# 261503933xxxx_HW-V1.net
KiCad netlist of a schematic drawn in EAGLE
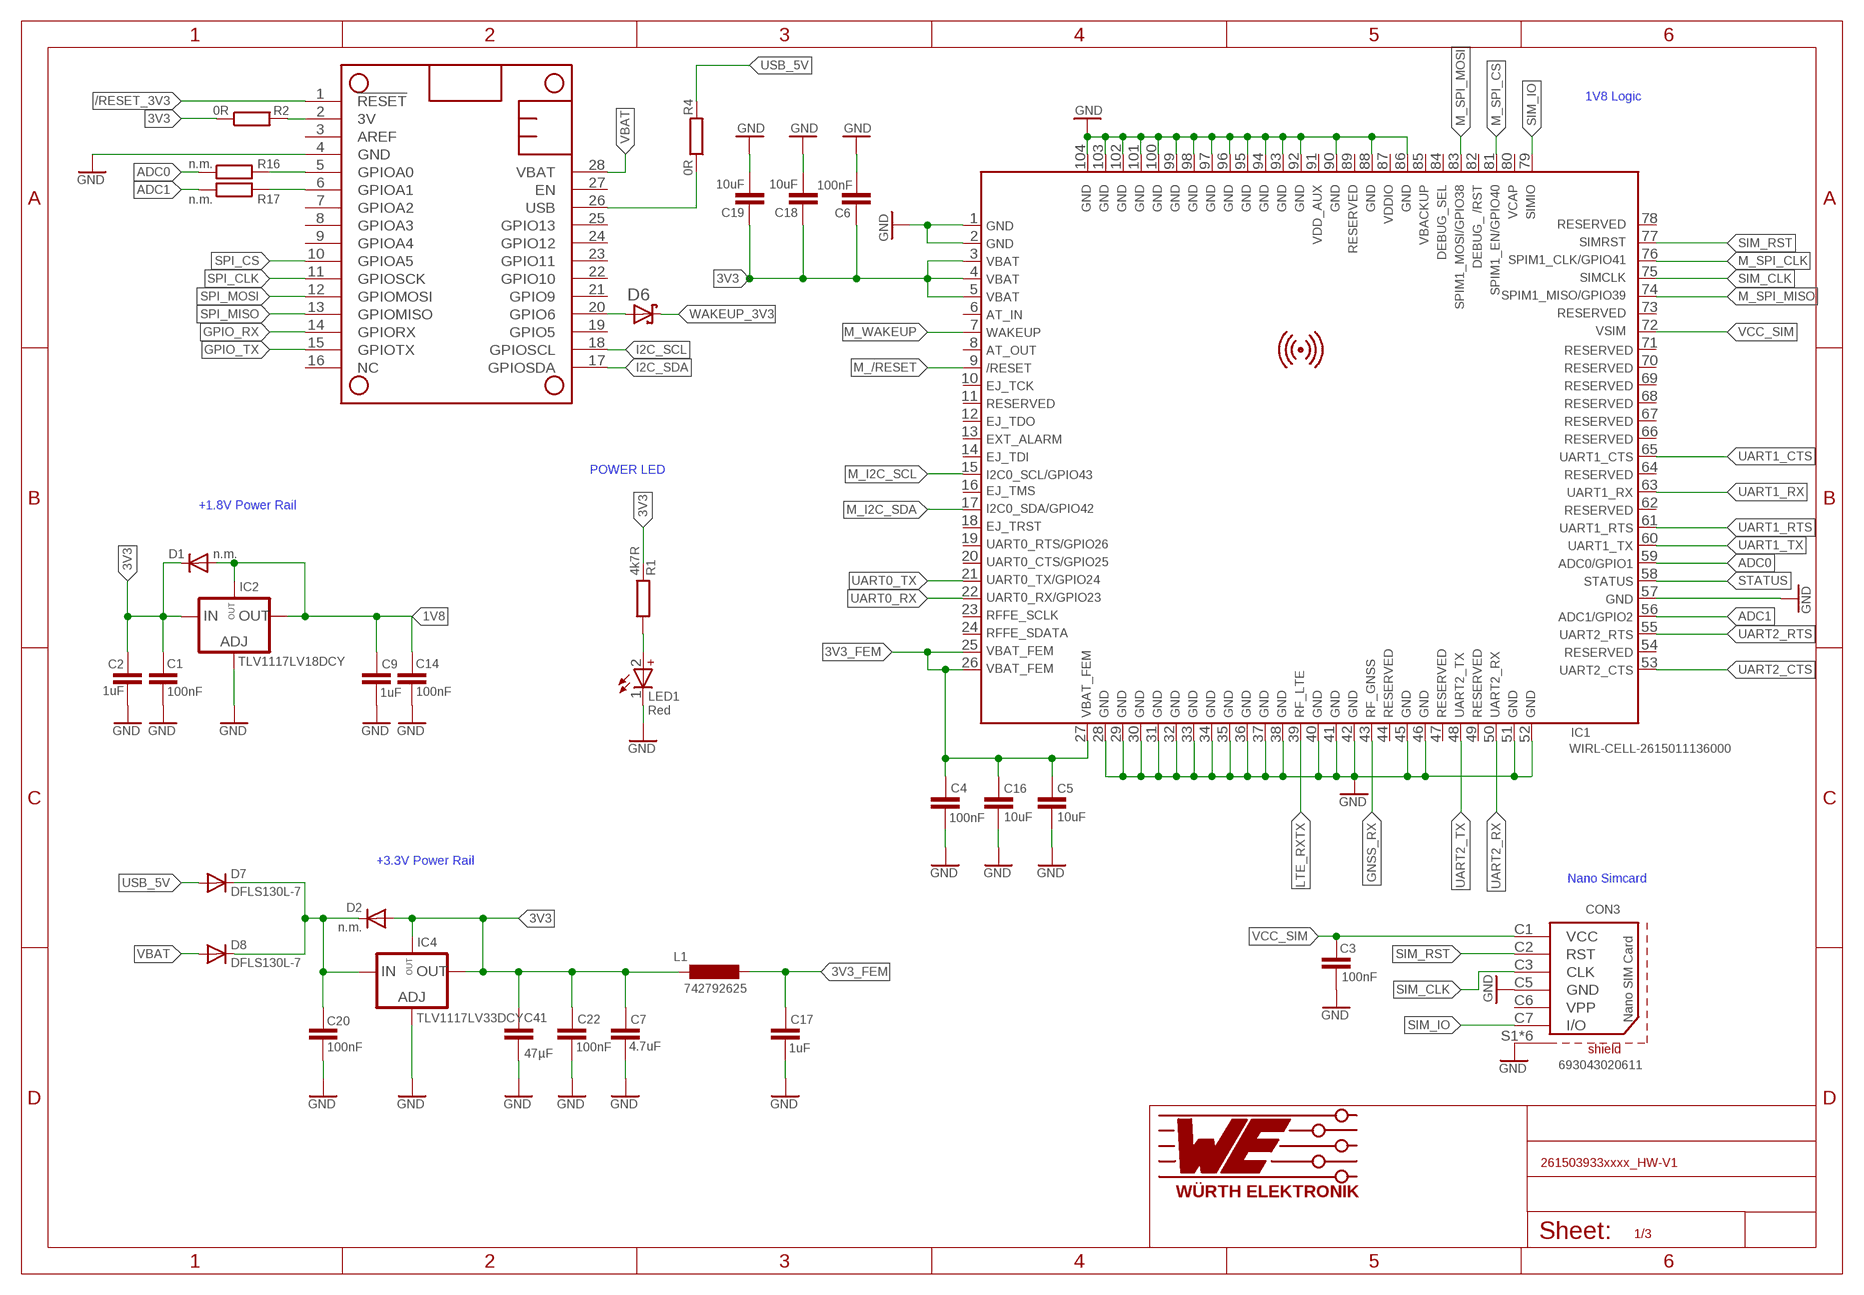
[diagram p0: schematic, sheet 1]
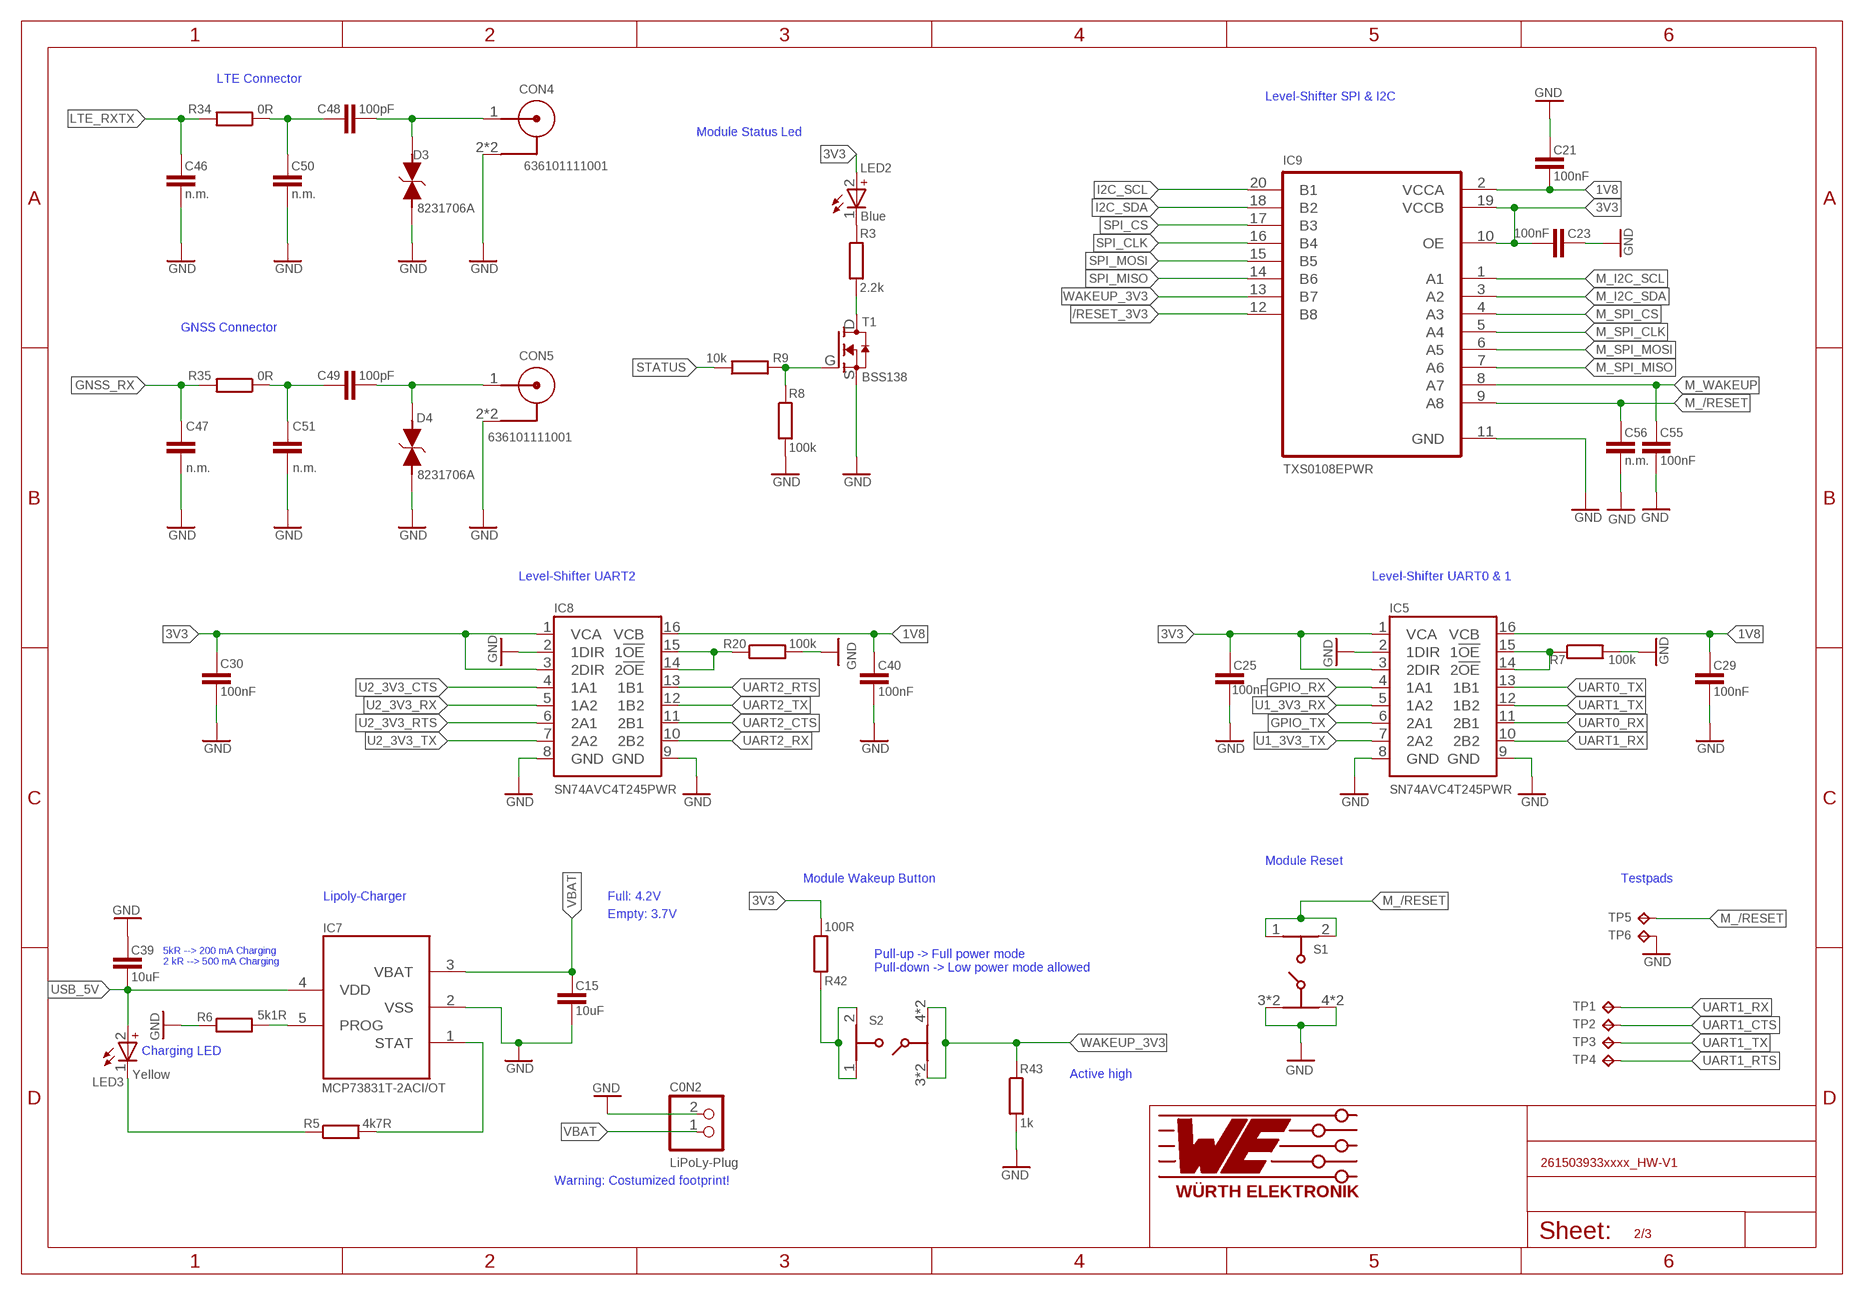
[diagram p1: schematic, sheet 2]
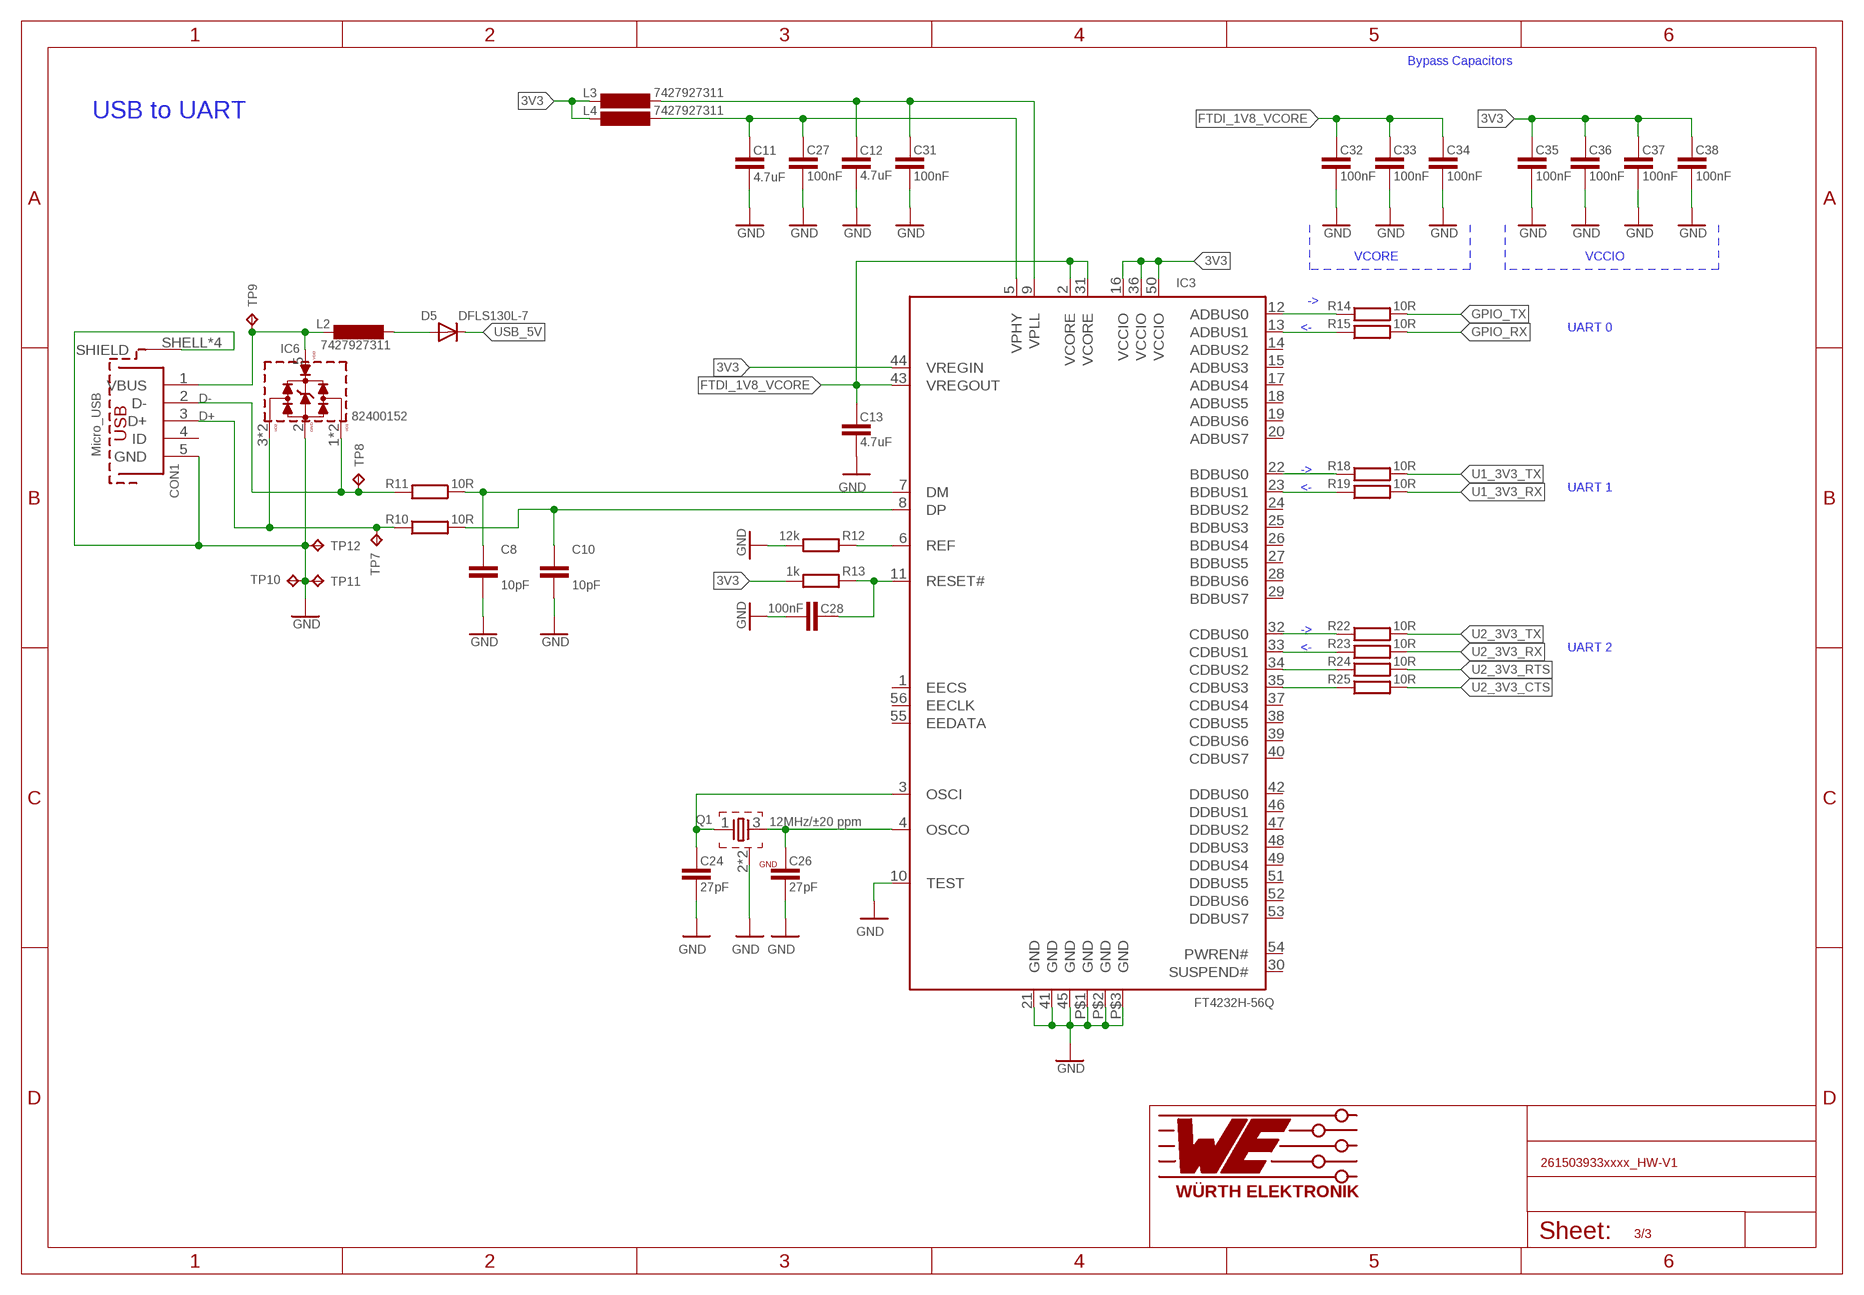
[diagram p2: schematic, sheet 3]

(export (version "E")
  (design (tool "Eeschema 10.0.6"))
  (components
    (comp (ref "C0N2")
      (value "LiPoLy-Plug")
      (footprint "eagle-import:JST-PH-2-SMT-RA-ADRASTEA-ANGEPASST")
      (fields (field (name "MANUFACTURER") "Adafruit"))
      (libsource (lib "eagle-import") (part "JST_2PIN"))
    )
    (comp (ref "C15")
      (value "10uF")
      (footprint "eagle-import:C0402_IPC")
      (fields (field (name "MANUFACTURER") "Würth Elektronik"))
      (libsource (lib "eagle-import") (part "C0402_IPC10UF"))
    )
    (comp (ref "C21")
      (value "100nF")
      (footprint "eagle-import:C0402_IPC")
      (fields
        (field (name "MANUFACTURER") "Würth Elektronik")
        (field (name "MAT") "X7R")
        (field (name "NR") "885012205037")
        (field (name "SPG") "16V")
        (field (name "TOL") "10%")
      )
      (libsource (lib "eagle-import") (part "rcl-amber_C0402_IPC"))
    )
    (comp (ref "C23")
      (value "100nF")
      (footprint "eagle-import:C0402_IPC")
      (fields
        (field (name "MANUFACTURER") "Würth Elektronik")
        (field (name "MAT") "X7R")
        (field (name "NR") "885012205037")
        (field (name "SPG") "16V")
        (field (name "TOL") "10%")
      )
      (libsource (lib "eagle-import") (part "rcl-amber_C0402_IPC"))
    )
    (comp (ref "C25")
      (value "100nF")
      (footprint "eagle-import:C0402_IPC")
      (fields
        (field (name "MANUFACTURER") "Würth Elektronik")
        (field (name "MAT") "X7R")
        (field (name "NR") "885012205037")
        (field (name "SPG") "16V")
        (field (name "TOL") "10%")
      )
      (libsource (lib "eagle-import") (part "rcl-amber_C0402_IPC"))
    )
    (comp (ref "C29")
      (value "100nF")
      (footprint "eagle-import:C0402_IPC")
      (fields
        (field (name "MANUFACTURER") "Würth Elektronik")
        (field (name "MAT") "X7R")
        (field (name "NR") "885012205037")
        (field (name "SPG") "16V")
        (field (name "TOL") "10%")
      )
      (libsource (lib "eagle-import") (part "rcl-amber_C0402_IPC"))
    )
    (comp (ref "C30")
      (value "100nF")
      (footprint "eagle-import:C0402_IPC")
      (fields
        (field (name "MANUFACTURER") "Würth Elektronik")
        (field (name "MAT") "X7R")
        (field (name "NR") "885012205037")
        (field (name "SPG") "16V")
        (field (name "TOL") "10%")
      )
      (libsource (lib "eagle-import") (part "rcl-amber_C0402_IPC"))
    )
    (comp (ref "C39")
      (value "10uF")
      (footprint "eagle-import:C0603_IPC")
      (fields (field (name "MANUFACTURER") "Wurth Elektronik") (field (name "NR") "885012106031"))
      (libsource (lib "eagle-import") (part "C0603_IPC1UF"))
    )
    (comp (ref "C40")
      (value "100nF")
      (footprint "eagle-import:C0402_IPC")
      (fields
        (field (name "MANUFACTURER") "Würth Elektronik")
        (field (name "MAT") "X7R")
        (field (name "NR") "885012205037")
        (field (name "SPG") "16V")
        (field (name "TOL") "10%")
      )
      (libsource (lib "eagle-import") (part "rcl-amber_C0402_IPC"))
    )
    (comp (ref "C46")
      (value "n.m.")
      (footprint "eagle-import:C0402_IPC")
      (fields (field (name "MANUFACTURER") "n.m.") (field (name "NR") "n.m."))
      (libsource (lib "eagle-import") (part "rcl-amber_C0402_IPC"))
    )
    (comp (ref "C47")
      (value "n.m.")
      (footprint "eagle-import:C0402_IPC")
      (fields (field (name "MANUFACTURER") "n.m.") (field (name "NR") "n.m."))
      (libsource (lib "eagle-import") (part "rcl-amber_C0402_IPC"))
    )
    (comp (ref "C48")
      (value "100pF")
      (footprint "eagle-import:C0402_IPC")
      (fields
        (field (name "MANUFACTURER") "Yageo")
        (field (name "MANUFACTURER_1") "Würth Elektronik")
        (field (name "MAT") "NP0")
        (field (name "NR") "885012005061")
      )
      (libsource (lib "eagle-import") (part "rcl-amber_C0402_IPC100PF"))
    )
    (comp (ref "C49")
      (value "100pF")
      (footprint "eagle-import:C0402_IPC")
      (fields
        (field (name "MANUFACTURER") "Würth Elektronik")
        (field (name "MAT") "NP0")
        (field (name "NR") "885012005061")
        (field (name "SPG") "50V")
        (field (name "TOL") "5%")
      )
      (libsource (lib "eagle-import") (part "rcl-amber_C0402_IPC"))
    )
    (comp (ref "C50")
      (value "n.m.")
      (footprint "eagle-import:C0402_IPC")
      (fields (field (name "MANUFACTURER") "n.m.") (field (name "NR") "n.m."))
      (libsource (lib "eagle-import") (part "rcl-amber_C0402_IPC"))
    )
    (comp (ref "C51")
      (value "n.m.")
      (footprint "eagle-import:C0402_IPC")
      (fields (field (name "MANUFACTURER") "n.m.") (field (name "NR") "n.m."))
      (libsource (lib "eagle-import") (part "rcl-amber_C0402_IPC"))
    )
    (comp (ref "C55")
      (value "100nF")
      (footprint "eagle-import:C0402_IPC")
      (fields
        (field (name "MANUFACTURER") "Würth Elektronik")
        (field (name "MAT") "X7R")
        (field (name "NR") "885012205037")
        (field (name "SPG") "16V")
        (field (name "TOL") "10%")
      )
      (libsource (lib "eagle-import") (part "rcl-amber_C0402_IPC"))
    )
    (comp (ref "C56")
      (value "n.m.")
      (footprint "eagle-import:C0402_IPC")
      (fields (field (name "MANUFACTURER") "n.m.") (field (name "NR") "n.m."))
      (libsource (lib "eagle-import") (part "rcl-amber_C0402_IPC"))
    )
    (comp (ref "CON4")
      (value "636101111001")
      (footprint "eagle-import:636101111001")
      (libsource (lib "eagle-import") (part "636101111001"))
    )
    (comp (ref "CON5")
      (value "636101111001")
      (footprint "eagle-import:636101111001")
      (libsource (lib "eagle-import") (part "636101111001"))
    )
    (comp (ref "D3")
      (value "8231706A")
      (footprint "eagle-import:WE-VE_FEMTOF_0402")
      (fields (field (name "MANUFACTURER") "Würth Elektronik"))
      (libsource (lib "eagle-import") (part "WE-VE_FEMTOF_0402_8231714A"))
    )
    (comp (ref "D4")
      (value "8231706A")
      (footprint "eagle-import:WE-VE_FEMTOF_0402")
      (fields (field (name "MANUFACTURER") "Würth Elektronik"))
      (libsource (lib "eagle-import") (part "WE-VE_FEMTOF_0402_8231714A"))
    )
    (comp (ref "IC5")
      (value "SN74AVC4T245PWR")
      (footprint "eagle-import:PW16(TSSOP16)")
      (fields (field (name "MANUFACTURER") "Texas Instruments"))
      (libsource (lib "eagle-import") (part "SN74AVC4T245PWR"))
    )
    (comp (ref "IC7")
      (value "MCP73831T-2ACI/OT")
      (footprint "eagle-import:SOT23-5")
      (fields (field (name "MANUFACTURER") "microchip"))
      (libsource (lib "eagle-import") (part "MCP73831T-2ACI/OT"))
    )
    (comp (ref "IC8")
      (value "SN74AVC4T245PWR")
      (footprint "eagle-import:PW16(TSSOP16)")
      (fields (field (name "MANUFACTURER") "Texas Instruments"))
      (libsource (lib "eagle-import") (part "SN74AVC4T245PWR"))
    )
    (comp (ref "IC9")
      (value "TXS0108EPWR")
      (footprint "eagle-import:SOP65P640X120-20N")
      (fields (field (name "MF") "Texas Instruments"))
      (libsource (lib "eagle-import") (part "TXS0108EPWR"))
    )
    (comp (ref "LED2")
      (value "Blue")
      (footprint "eagle-import:WL-SMSW_1204_A")
      (fields (field (name "MANUFACTURER") "würth elektronik"))
      (libsource (lib "eagle-import") (part "WL-SMSW_1204_155124BS73200"))
    )
    (comp (ref "LED3")
      (value "Yellow")
      (footprint "eagle-import:WL-SMSW_1204_A")
      (fields (field (name "MANUFACTURER") "würth elektronik"))
      (libsource (lib "eagle-import") (part "WL-SMSW_1204_155124RS73200"))
    )
    (comp (ref "R3")
      (value "2.2k")
      (footprint "eagle-import:R0402_IPC")
      (fields (field (name "MANUFACTURER") "Yageo") (field (name "P") "1/16W"))
      (libsource (lib "eagle-import") (part "R0402_IPC2K2"))
    )
    (comp (ref "R5")
      (value "4k7R")
      (footprint "eagle-import:R0402_IPC")
      (fields (field (name "MANUFACTURER") "Yageo"))
      (libsource (lib "eagle-import") (part "R0402_IPC4K7"))
    )
    (comp (ref "R6")
      (value "5k1R")
      (footprint "eagle-import:R0402_IPC")
      (fields (field (name "NR") " RC0402FR-075K1L"))
      (libsource (lib "eagle-import") (part "R0402_IPC56R"))
    )
    (comp (ref "R7")
      (value "100k")
      (footprint "eagle-import:R0402_IPC")
      (libsource (lib "eagle-import") (part "R0402_IPC100KR"))
    )
    (comp (ref "R8")
      (value "100k")
      (footprint "eagle-import:R0402_IPC")
      (fields (field (name "MANUFACTURER") "Yageo") (field (name "P") "1/16W"))
      (libsource (lib "eagle-import") (part "rcl-amber_R0402_IPC100KR"))
    )
    (comp (ref "R9")
      (value "10k")
      (footprint "eagle-import:R0402_IPC")
      (fields (field (name "MANUFACTURER") "Yageo") (field (name "P") "1/16W"))
      (libsource (lib "eagle-import") (part "rcl-amber_R0402_IPC10KR"))
    )
    (comp (ref "R20")
      (value "100k")
      (footprint "eagle-import:R0402_IPC")
      (libsource (lib "eagle-import") (part "R0402_IPC100KR"))
    )
    (comp (ref "R34")
      (value "0R")
      (footprint "eagle-import:R0402_IPC")
      (fields (field (name "MANUFACTURER") "Yageo") (field (name "P") "1/16W"))
      (libsource (lib "eagle-import") (part "rcl-amber_R0402_IPC0R"))
    )
    (comp (ref "R35")
      (value "0R")
      (footprint "eagle-import:R0402_IPC")
      (fields (field (name "MANUFACTURER") "Yageo") (field (name "P") "1/16W"))
      (libsource (lib "eagle-import") (part "rcl-amber_R0402_IPC0R"))
    )
    (comp (ref "R42")
      (value "100R")
      (footprint "eagle-import:R0402_IPC")
      (fields (field (name "MANUFACTURER") "Yageo"))
      (libsource (lib "eagle-import") (part "R0402_IPC100R"))
    )
    (comp (ref "R43")
      (value "1k")
      (footprint "eagle-import:R0402_IPC")
      (fields (field (name "MANUFACTURER") "Yageo") (field (name "P") "1/16W"))
      (libsource (lib "eagle-import") (part "R0402_IPC1K"))
    )
    (comp (ref "S1")
      (value "434331013822")
      (footprint "eagle-import:434331013822")
      (libsource (lib "eagle-import") (part "434331013822"))
    )
    (comp (ref "S2")
      (value "434331013822")
      (footprint "eagle-import:434331013822")
      (libsource (lib "eagle-import") (part "434331013822"))
    )
    (comp (ref "T1")
      (value "BSS138")
      (footprint "eagle-import:BSS138")
      (fields (field (name "MANUFACTURER") "ON seminconductor"))
      (libsource (lib "eagle-import") (part "BSS138"))
    )
    (comp (ref "TP1")
      (value "TP15R")
      (footprint "eagle-import:TP15R")
      (libsource (lib "eagle-import") (part "TP15R"))
    )
    (comp (ref "TP2")
      (value "TP15R")
      (footprint "eagle-import:TP15R")
      (libsource (lib "eagle-import") (part "TP15R"))
    )
    (comp (ref "TP3")
      (value "TP15R")
      (footprint "eagle-import:TP15R")
      (libsource (lib "eagle-import") (part "TP15R"))
    )
    (comp (ref "TP4")
      (value "TP15R")
      (footprint "eagle-import:TP15R")
      (libsource (lib "eagle-import") (part "TP15R"))
    )
    (comp (ref "TP5")
      (value "TP15R")
      (footprint "eagle-import:TP15R")
      (libsource (lib "eagle-import") (part "TP15R"))
    )
    (comp (ref "TP6")
      (value "TP15R")
      (footprint "eagle-import:TP15R")
      (libsource (lib "eagle-import") (part "TP15R"))
    )
    (comp (ref "C8")
      (value "10pF")
      (footprint "eagle-import:C0402_IPC")
      (fields (field (name "MANUFACTURER") "Würth Elektronik") (field (name "MAT") "NP0"))
      (libsource (lib "eagle-import") (part "C0402_IPC10PF"))
    )
    (comp (ref "C10")
      (value "10pF")
      (footprint "eagle-import:C0402_IPC")
      (fields (field (name "MANUFACTURER") "Würth Elektronik") (field (name "MAT") "NP0"))
      (libsource (lib "eagle-import") (part "C0402_IPC10PF"))
    )
    (comp (ref "C11")
      (value "4.7uF")
      (footprint "eagle-import:C0402_IPC")
      (fields (field (name "MANUFACTURER") "Würth Elektronik"))
      (libsource (lib "eagle-import") (part "C0402_IPC4.7UF"))
    )
    (comp (ref "C12")
      (value "4.7uF")
      (footprint "eagle-import:C0402_IPC")
      (fields (field (name "MANUFACTURER") "Würth Elektronik"))
      (libsource (lib "eagle-import") (part "C0402_IPC4.7UF"))
    )
    (comp (ref "C13")
      (value "4.7uF")
      (footprint "eagle-import:C0402_IPC")
      (fields (field (name "MANUFACTURER") "Würth Elektronik"))
      (libsource (lib "eagle-import") (part "C0402_IPC4.7UF"))
    )
    (comp (ref "C24")
      (value "27pF")
      (footprint "eagle-import:C0402_IPC")
      (fields
        (field (name "MANUFACTURER") "Yageo")
        (field (name "MANUFACTURER_1") "Samsung")
        (field (name "NR") "CL05C270JB5NNNC")
      )
      (libsource (lib "eagle-import") (part "C0402_IPC27P"))
    )
    (comp (ref "C26")
      (value "27pF")
      (footprint "eagle-import:C0402_IPC")
      (fields
        (field (name "MANUFACTURER") "Yageo")
        (field (name "MANUFACTURER_1") "Samsung")
        (field (name "NR") "CL05C270JB5NNNC")
      )
      (libsource (lib "eagle-import") (part "C0402_IPC27P"))
    )
    (comp (ref "C27")
      (value "100nF")
      (footprint "eagle-import:C0402_IPC")
      (fields
        (field (name "MANUFACTURER") "Würth Elektronik")
        (field (name "MAT") "X7R")
        (field (name "NR") "885012205037")
        (field (name "SPG") "16V")
        (field (name "TOL") "10%")
      )
      (libsource (lib "eagle-import") (part "rcl-amber_C0402_IPC"))
    )
    (comp (ref "C28")
      (value "100nF")
      (footprint "eagle-import:C0402_IPC")
      (fields
        (field (name "MANUFACTURER") "Würth Elektronik")
        (field (name "MAT") "X7R")
        (field (name "NR") "885012205037")
        (field (name "SPG") "16V")
        (field (name "TOL") "10%")
      )
      (libsource (lib "eagle-import") (part "rcl-amber_C0402_IPC"))
    )
    (comp (ref "C31")
      (value "100nF")
      (footprint "eagle-import:C0402_IPC")
      (fields
        (field (name "MANUFACTURER") "Würth Elektronik")
        (field (name "MAT") "X7R")
        (field (name "NR") "885012205037")
        (field (name "SPG") "16V")
        (field (name "TOL") "10%")
      )
      (libsource (lib "eagle-import") (part "rcl-amber_C0402_IPC"))
    )
    (comp (ref "C32")
      (value "100nF")
      (footprint "eagle-import:C0402_IPC")
      (fields
        (field (name "MANUFACTURER") "Würth Elektronik")
        (field (name "MAT") "X7R")
        (field (name "NR") "885012205037")
        (field (name "SPG") "16V")
        (field (name "TOL") "10%")
      )
      (libsource (lib "eagle-import") (part "rcl-amber_C0402_IPC"))
    )
    (comp (ref "C33")
      (value "100nF")
      (footprint "eagle-import:C0402_IPC")
      (fields
        (field (name "MANUFACTURER") "Würth Elektronik")
        (field (name "MAT") "X7R")
        (field (name "NR") "885012205037")
        (field (name "SPG") "16V")
        (field (name "TOL") "10%")
      )
      (libsource (lib "eagle-import") (part "rcl-amber_C0402_IPC"))
    )
    (comp (ref "C34")
      (value "100nF")
      (footprint "eagle-import:C0402_IPC")
      (fields
        (field (name "MANUFACTURER") "Würth Elektronik")
        (field (name "MAT") "X7R")
        (field (name "NR") "885012205037")
        (field (name "SPG") "16V")
        (field (name "TOL") "10%")
      )
      (libsource (lib "eagle-import") (part "rcl-amber_C0402_IPC"))
    )
    (comp (ref "C35")
      (value "100nF")
      (footprint "eagle-import:C0402_IPC")
      (fields
        (field (name "MANUFACTURER") "Würth Elektronik")
        (field (name "MAT") "X7R")
        (field (name "NR") "885012205037")
        (field (name "SPG") "16V")
        (field (name "TOL") "10%")
      )
      (libsource (lib "eagle-import") (part "rcl-amber_C0402_IPC"))
    )
    (comp (ref "C36")
      (value "100nF")
      (footprint "eagle-import:C0402_IPC")
      (fields
        (field (name "MANUFACTURER") "Würth Elektronik")
        (field (name "MAT") "X7R")
        (field (name "NR") "885012205037")
        (field (name "SPG") "16V")
        (field (name "TOL") "10%")
      )
      (libsource (lib "eagle-import") (part "rcl-amber_C0402_IPC"))
    )
    (comp (ref "C37")
      (value "100nF")
      (footprint "eagle-import:C0402_IPC")
      (fields
        (field (name "MANUFACTURER") "Würth Elektronik")
        (field (name "MAT") "X7R")
        (field (name "NR") "885012205037")
        (field (name "SPG") "16V")
        (field (name "TOL") "10%")
      )
      (libsource (lib "eagle-import") (part "rcl-amber_C0402_IPC"))
    )
    (comp (ref "C38")
      (value "100nF")
      (footprint "eagle-import:C0402_IPC")
      (fields
        (field (name "MANUFACTURER") "Würth Elektronik")
        (field (name "MAT") "X7R")
        (field (name "NR") "885012205037")
        (field (name "SPG") "16V")
        (field (name "TOL") "10%")
      )
      (libsource (lib "eagle-import") (part "rcl-amber_C0402_IPC"))
    )
    (comp (ref "CON1")
      (value "Micro_USB")
      (footprint "eagle-import:629105150521")
      (fields
        (field (name "COMMENT") "Use selective soldering")
        (field (name "MANUFACTURER") "Würth Elektronik")
      )
      (libsource (lib "eagle-import") (part "629105150521"))
    )
    (comp (ref "D5")
      (value "DFLS130L-7")
      (footprint "eagle-import:SOD123_POWERDI")
      (fields (field (name "MANUFACTURER") "diodes inc"))
      (libsource (lib "eagle-import") (part "DFLS130L-7"))
    )
    (comp (ref "IC3")
      (value "FT4232H-56Q")
      (footprint "eagle-import:VQFN-56")
      (fields (field (name "MANUFACTURER") "FTDI"))
      (libsource (lib "eagle-import") (part "FT4232H-56Q"))
    )
    (comp (ref "IC6")
      (value "82400152")
      (footprint "eagle-import:WE-TVS_SOT563")
      (fields (field (name "MANUFACTURER") "Würth Elektronik"))
      (libsource (lib "eagle-import") (part "WE-TVS_82400152"))
    )
    (comp (ref "L2")
      (value "7427927311")
      (footprint "eagle-import:L0402_WE-MK")
      (fields
        (field (name "MANUFACTURER") "Tayo Yuden")
        (field (name "MANUFACTURER_1") "Würth Elektronik")
        (field (name "NR") "7427927311")
      )
      (libsource (lib "eagle-import") (part "LL0402_WE-MK"))
    )
    (comp (ref "L3")
      (value "7427927311")
      (footprint "eagle-import:L0402_WE-MK")
      (fields
        (field (name "MANUFACTURER") "Tayo Yuden")
        (field (name "MANUFACTURER_1") "Würth Elektronik")
        (field (name "NR") "7427927311")
      )
      (libsource (lib "eagle-import") (part "LL0402_WE-MK"))
    )
    (comp (ref "L4")
      (value "7427927311")
      (footprint "eagle-import:L0402_WE-MK")
      (fields
        (field (name "MANUFACTURER") "Tayo Yuden")
        (field (name "MANUFACTURER_1") "Würth Elektronik")
        (field (name "NR") "7427927311")
      )
      (libsource (lib "eagle-import") (part "LL0402_WE-MK"))
    )
    (comp (ref "Q1")
      (value "12MHz/±20 ppm")
      (footprint "eagle-import:WE-XTAL_CFPX-180")
      (fields (field (name "MANUFACTURER") "Würth Elektronik"))
      (libsource (lib "eagle-import") (part "WE-XTAL_CFPX-180_830070868"))
    )
    (comp (ref "R10")
      (value "10R")
      (footprint "eagle-import:R0402_IPC")
      (fields (field (name "MANUFACTURER") "Yageo"))
      (libsource (lib "eagle-import") (part "rcl-amber_R0402_IPC10R"))
    )
    (comp (ref "R11")
      (value "10R")
      (footprint "eagle-import:R0402_IPC")
      (fields (field (name "MANUFACTURER") "Yageo"))
      (libsource (lib "eagle-import") (part "rcl-amber_R0402_IPC10R"))
    )
    (comp (ref "R12")
      (value "12k")
      (footprint "eagle-import:R0402_IPC")
      (fields (field (name "MANUFACTURER") "Yageo") (field (name "P") "1/16W"))
      (libsource (lib "eagle-import") (part "R0402_IPC12K"))
    )
    (comp (ref "R13")
      (value "1k")
      (footprint "eagle-import:R0402_IPC")
      (fields (field (name "MANUFACTURER") "Yageo"))
      (libsource (lib "eagle-import") (part "R0402_IPC1K"))
    )
    (comp (ref "R14")
      (value "10R")
      (footprint "eagle-import:R0402_IPC")
      (fields (field (name "MANUFACTURER") "Yageo"))
      (libsource (lib "eagle-import") (part "rcl-amber_R0402_IPC10R"))
    )
    (comp (ref "R15")
      (value "10R")
      (footprint "eagle-import:R0402_IPC")
      (fields (field (name "MANUFACTURER") "Yageo"))
      (libsource (lib "eagle-import") (part "rcl-amber_R0402_IPC10R"))
    )
    (comp (ref "R18")
      (value "10R")
      (footprint "eagle-import:R0402_IPC")
      (fields (field (name "MANUFACTURER") "Yageo"))
      (libsource (lib "eagle-import") (part "rcl-amber_R0402_IPC10R"))
    )
    (comp (ref "R19")
      (value "10R")
      (footprint "eagle-import:R0402_IPC")
      (fields (field (name "MANUFACTURER") "Yageo"))
      (libsource (lib "eagle-import") (part "rcl-amber_R0402_IPC10R"))
    )
    (comp (ref "R22")
      (value "10R")
      (footprint "eagle-import:R0402_IPC")
      (fields (field (name "MANUFACTURER") "Yageo"))
      (libsource (lib "eagle-import") (part "rcl-amber_R0402_IPC10R"))
    )
    (comp (ref "R23")
      (value "10R")
      (footprint "eagle-import:R0402_IPC")
      (fields (field (name "MANUFACTURER") "Yageo"))
      (libsource (lib "eagle-import") (part "rcl-amber_R0402_IPC10R"))
    )
    (comp (ref "R24")
      (value "10R")
      (footprint "eagle-import:R0402_IPC")
      (fields (field (name "MANUFACTURER") "Yageo"))
      (libsource (lib "eagle-import") (part "rcl-amber_R0402_IPC10R"))
    )
    (comp (ref "R25")
      (value "10R")
      (footprint "eagle-import:R0402_IPC")
      (fields (field (name "MANUFACTURER") "Yageo"))
      (libsource (lib "eagle-import") (part "rcl-amber_R0402_IPC10R"))
    )
    (comp (ref "TP7")
      (value "TP15R")
      (footprint "eagle-import:TP15R")
      (libsource (lib "eagle-import") (part "TP15R"))
    )
    (comp (ref "TP8")
      (value "TP15R")
      (footprint "eagle-import:TP15R")
      (libsource (lib "eagle-import") (part "TP15R"))
    )
    (comp (ref "TP9")
      (value "TP15R")
      (footprint "eagle-import:TP15R")
      (libsource (lib "eagle-import") (part "TP15R"))
    )
    (comp (ref "TP10")
      (value "TP15R")
      (footprint "eagle-import:TP15R")
      (libsource (lib "eagle-import") (part "TP15R"))
    )
    (comp (ref "TP11")
      (value "TP15R")
      (footprint "eagle-import:TP15R")
      (libsource (lib "eagle-import") (part "TP15R"))
    )
    (comp (ref "TP12")
      (value "TP15R")
      (footprint "eagle-import:TP15R")
      (libsource (lib "eagle-import") (part "TP15R"))
    )
    (comp (ref "C1")
      (value "100nF")
      (footprint "eagle-import:C0402_IPC")
      (fields
        (field (name "MANUFACTURER") "Würth Elektronik")
        (field (name "MAT") "X7R")
        (field (name "NR") "885012205037")
        (field (name "SPG") "16V")
        (field (name "TOL") "10%")
      )
      (libsource (lib "eagle-import") (part "rcl-amber_C0402_IPC"))
    )
    (comp (ref "C2")
      (value "1uF")
      (footprint "eagle-import:C0402_IPC")
      (fields (field (name "MANUFACTURER") "Würth Elektronik"))
      (libsource (lib "eagle-import") (part "C0402_IPC1UF"))
    )
    (comp (ref "C3")
      (value "100nF")
      (footprint "eagle-import:C0402_IPC")
      (fields (field (name "MANUFACTURER") "Würth Elektronik"))
      (libsource (lib "eagle-import") (part "C0402_IPC100NF"))
    )
    (comp (ref "C4")
      (value "100nF")
      (footprint "eagle-import:C0402_IPC")
      (fields
        (field (name "MANUFACTURER") "Würth Elektronik")
        (field (name "MAT") "X7R")
        (field (name "NR") "885012205037")
        (field (name "SPG") "16V")
        (field (name "TOL") "10%")
      )
      (libsource (lib "eagle-import") (part "rcl-amber_C0402_IPC"))
    )
    (comp (ref "C5")
      (value "10uF")
      (footprint "eagle-import:C0402_IPC")
      (fields
        (field (name "MANUFACTURER") "Würth Elektronik")
        (field (name "NR") "885012105020")
        (field (name "SPG") "6,3V")
      )
      (libsource (lib "eagle-import") (part "C0402_IPC"))
    )
    (comp (ref "C6")
      (value "100nF")
      (footprint "eagle-import:C0402_IPC")
      (fields
        (field (name "MANUFACTURER") "Würth Elektronik")
        (field (name "MAT") "X7R")
        (field (name "NR") "885012205037")
        (field (name "SPG") "16V")
        (field (name "TOL") "10%")
      )
      (libsource (lib "eagle-import") (part "rcl-amber_C0402_IPC"))
    )
    (comp (ref "C7")
      (value "4.7uF")
      (footprint "eagle-import:C0402_IPC")
      (fields (field (name "MANUFACTURER") "Würth Elektronik"))
      (libsource (lib "eagle-import") (part "C0402_IPC4.7UF"))
    )
    (comp (ref "C9")
      (value "1uF")
      (footprint "eagle-import:C0402_IPC")
      (fields (field (name "MANUFACTURER") "Würth Elektronik"))
      (libsource (lib "eagle-import") (part "C0402_IPC1UF"))
    )
    (comp (ref "C14")
      (value "100nF")
      (footprint "eagle-import:C0402_IPC")
      (fields
        (field (name "MANUFACTURER") "Würth Elektronik")
        (field (name "MAT") "X7R")
        (field (name "NR") "885012205037")
        (field (name "SPG") "16V")
        (field (name "TOL") "10%")
      )
      (libsource (lib "eagle-import") (part "rcl-amber_C0402_IPC"))
    )
    (comp (ref "C16")
      (value "10uF")
      (footprint "eagle-import:C0402_IPC")
      (fields
        (field (name "MANUFACTURER") "Würth Elektronik")
        (field (name "MAT") "X5R")
        (field (name "NR") "885012105020")
        (field (name "SPG") "6,3V")
        (field (name "TOL") "20%")
      )
      (libsource (lib "eagle-import") (part "C0402_IPC"))
    )
    (comp (ref "C17")
      (value "1uF")
      (footprint "eagle-import:C0402_IPC")
      (fields (field (name "MANUFACTURER") "Würth Elektronik"))
      (libsource (lib "eagle-import") (part "C0402_IPC1UF"))
    )
    (comp (ref "C18")
      (value "10uF")
      (footprint "eagle-import:C0402_IPC")
      (fields
        (field (name "MANUFACTURER") "Würth Elektronik")
        (field (name "NR") "885012105020")
        (field (name "SPG") "6,3V")
      )
      (libsource (lib "eagle-import") (part "C0402_IPC"))
    )
    (comp (ref "C19")
      (value "10uF")
      (footprint "eagle-import:C0402_IPC")
      (fields
        (field (name "MANUFACTURER") "Würth Elektronik")
        (field (name "NR") "885012105020")
        (field (name "SPG") "6,3V")
      )
      (libsource (lib "eagle-import") (part "C0402_IPC"))
    )
    (comp (ref "C20")
      (value "100nF")
      (footprint "eagle-import:C0402_IPC")
      (fields
        (field (name "MANUFACTURER") "Würth Elektronik")
        (field (name "MAT") "X7R")
        (field (name "NR") "885012205037")
        (field (name "SPG") "16V")
        (field (name "TOL") "10%")
      )
      (libsource (lib "eagle-import") (part "rcl-amber_C0402_IPC"))
    )
    (comp (ref "C22")
      (value "100nF")
      (footprint "eagle-import:C0402_IPC")
      (fields
        (field (name "MANUFACTURER") "Würth Elektronik")
        (field (name "MAT") "X7R")
        (field (name "NR") "885012205037")
        (field (name "SPG") "16V")
        (field (name "TOL") "10%")
      )
      (libsource (lib "eagle-import") (part "rcl-amber_C0402_IPC"))
    )
    (comp (ref "C41")
      (value "47µF")
      (footprint "eagle-import:C0805")
      (fields (field (name "MANUFACTURER") "Wurth Elektronik"))
      (libsource (lib "eagle-import") (part "C080547UF"))
    )
    (comp (ref "CON3")
      (value "693043020611")
      (footprint "eagle-import:693043020611")
      (libsource (lib "eagle-import") (part "693043020611"))
    )
    (comp (ref "D1")
      (value "n.m.")
      (footprint "eagle-import:SOT23@1")
      (libsource (lib "eagle-import") (part "BAS16"))
    )
    (comp (ref "D2")
      (value "n.m.")
      (footprint "eagle-import:SOT23@1")
      (libsource (lib "eagle-import") (part "BAS16"))
    )
    (comp (ref "D6")
      (value "BAT540402_X1-DFN1006-2")
      (footprint "eagle-import:X1-DFN1006-2")
      (fields (field (name "MANUFACTURER") "Diodes Inc."))
      (libsource (lib "eagle-import") (part "BAT540402_X1-DFN1006-2"))
    )
    (comp (ref "D7")
      (value "DFLS130L-7")
      (footprint "eagle-import:SOD123_POWERDI")
      (fields (field (name "MANUFACTURER") "diodes inc"))
      (libsource (lib "eagle-import") (part "DFLS130L-7"))
    )
    (comp (ref "D8")
      (value "DFLS130L-7")
      (footprint "eagle-import:SOD123_POWERDI")
      (fields (field (name "MANUFACTURER") "diodes inc"))
      (libsource (lib "eagle-import") (part "DFLS130L-7"))
    )
    (comp (ref "IC1")
      (value "WIRL-CELL-2615011136000")
      (footprint "eagle-import:WIRL-CELL-2615011136000")
      (fields (field (name "MANUFACTURER") "Wuerth Elektronik"))
      (libsource (lib "eagle-import") (part "WIRL-CELL-2615011136000"))
    )
    (comp (ref "IC2")
      (value "TLV1117LV18DCY")
      (footprint "eagle-import:SOT223-4")
      (fields (field (name "MANUFACTURER") "Texas Instruments"))
      (libsource (lib "eagle-import") (part "TLV1117-XXIDCYR"))
    )
    (comp (ref "IC4")
      (value "TLV1117LV33DCY")
      (footprint "eagle-import:SOT223-4")
      (fields (field (name "MANUFACTURER") "Texas Instruments"))
      (libsource (lib "eagle-import") (part "TLV1117-XXIDCYR"))
    )
    (comp (ref "L1")
      (value "742792625")
      (footprint "eagle-import:L0603_WE-MK")
      (fields
        (field (name "ISAT") "1.5A")
        (field (name "MANUFACTURER") "Würth Elektronik")
        (field (name "NR") "742792625")
        (field (name "RDC") "0.05R")
        (field (name "TOL") "25%")
      )
      (libsource (lib "eagle-import") (part "LL0603_WE-MK"))
    )
    (comp (ref "LED1")
      (value "Red")
      (footprint "eagle-import:WL-SMSW_1204_A")
      (fields (field (name "MANUFACTURER") "würth elektronik"))
      (libsource (lib "eagle-import") (part "WL-SMSW_1204_155124RS73200"))
    )
    (comp (ref "MS1")
      (value "FEATHERWING_80MM")
      (footprint "eagle-import:FEATHERWING_80MM")
      (libsource (lib "eagle-import") (part "FEATHERWING_80MM"))
    )
    (comp (ref "R1")
      (value "4k7R")
      (footprint "eagle-import:R0402_IPC")
      (fields (field (name "MANUFACTURER") "Yageo"))
      (libsource (lib "eagle-import") (part "R0402_IPC4K7"))
    )
    (comp (ref "R2")
      (value "0R")
      (footprint "eagle-import:R0603_IPC")
      (fields (field (name "MANUFACTURER") "Yageo"))
      (libsource (lib "eagle-import") (part "R0603_IPC0R"))
    )
    (comp (ref "R4")
      (value "0R")
      (footprint "eagle-import:R0603_IPC")
      (fields (field (name "MANUFACTURER") "Yageo"))
      (libsource (lib "eagle-import") (part "R0603_IPC0R"))
    )
    (comp (ref "R16")
      (value "n.m.")
      (footprint "eagle-import:R0402_IPC")
      (libsource (lib "eagle-import") (part "R0402_IPC"))
    )
    (comp (ref "R17")
      (value "n.m.")
      (footprint "eagle-import:R0402_IPC")
      (libsource (lib "eagle-import") (part "R0402_IPC"))
    )
  )
  (nets
    (net (code "1") (name "1V8") (class "Default")
      (node (ref "C14") (pin "2") (pinfunction "2_2") (pintype "passive"))
      (node (ref "C21") (pin "1") (pinfunction "1_1") (pintype "passive"))
      (node (ref "C29") (pin "2") (pinfunction "2_2") (pintype "passive"))
      (node (ref "C40") (pin "2") (pinfunction "2_2") (pintype "passive"))
      (node (ref "C9") (pin "1") (pinfunction "1_1") (pintype "passive"))
      (node (ref "D1") (pin "1") (pinfunction "A_1") (pintype "passive"))
      (node (ref "IC2") (pin "2") (pinfunction "OUT_2") (pintype "passive"))
      (node (ref "IC2") (pin "4") (pinfunction "OUT_4") (pintype "bidirectional"))
      (node (ref "IC5") (pin "16") (pinfunction "VCB_16") (pintype "bidirectional"))
      (node (ref "IC8") (pin "16") (pinfunction "VCB_16") (pintype "bidirectional"))
      (node (ref "IC9") (pin "2") (pinfunction "VCCA_2") (pintype "power_in"))
    )
    (net (code "2") (name "3V3") (class "Default")
      (node (ref "C1") (pin "2") (pinfunction "2_2") (pintype "passive"))
      (node (ref "C18") (pin "1") (pinfunction "1_1") (pintype "passive"))
      (node (ref "C19") (pin "1") (pinfunction "1_1") (pintype "passive"))
      (node (ref "C2") (pin "1") (pinfunction "1_1") (pintype "passive"))
      (node (ref "C22") (pin "2") (pinfunction "2_2") (pintype "passive"))
      (node (ref "C23") (pin "1") (pinfunction "1_1") (pintype "passive"))
      (node (ref "C25") (pin "2") (pinfunction "2_2") (pintype "passive"))
      (node (ref "C30") (pin "2") (pinfunction "2_2") (pintype "passive"))
      (node (ref "C35") (pin "2") (pinfunction "2_2") (pintype "passive"))
      (node (ref "C36") (pin "2") (pinfunction "2_2") (pintype "passive"))
      (node (ref "C37") (pin "2") (pinfunction "2_2") (pintype "passive"))
      (node (ref "C38") (pin "2") (pinfunction "2_2") (pintype "passive"))
      (node (ref "C41") (pin "P$1") (pinfunction "1_P$1") (pintype "passive"))
      (node (ref "C6") (pin "2") (pinfunction "2_2") (pintype "passive"))
      (node (ref "C7") (pin "1") (pinfunction "1_1") (pintype "passive"))
      (node (ref "D1") (pin "3") (pinfunction "C_3") (pintype "passive"))
      (node (ref "D2") (pin "1") (pinfunction "A_1") (pintype "passive"))
      (node (ref "IC1") (pin "3") (pinfunction "VBAT_3") (pintype "bidirectional"))
      (node (ref "IC1") (pin "4") (pinfunction "VBAT_4") (pintype "bidirectional"))
      (node (ref "IC1") (pin "5") (pinfunction "VBAT_5") (pintype "bidirectional"))
      (node (ref "IC2") (pin "3") (pinfunction "IN_3") (pintype "input"))
      (node (ref "IC3") (pin "16") (pinfunction "VCCIO_16") (pintype "power_in"))
      (node (ref "IC3") (pin "36") (pinfunction "VCCIO_36") (pintype "power_in"))
      (node (ref "IC3") (pin "44") (pinfunction "VREGIN_44") (pintype "power_in"))
      (node (ref "IC3") (pin "50") (pinfunction "VCCIO_50") (pintype "power_in"))
      (node (ref "IC4") (pin "2") (pinfunction "OUT_2") (pintype "passive"))
      (node (ref "IC4") (pin "4") (pinfunction "OUT_4") (pintype "bidirectional"))
      (node (ref "IC5") (pin "1") (pinfunction "VCA_1") (pintype "bidirectional"))
      (node (ref "IC5") (pin "3") (pinfunction "2DIR_3") (pintype "bidirectional"))
      (node (ref "IC8") (pin "1") (pinfunction "VCA_1") (pintype "bidirectional"))
      (node (ref "IC8") (pin "3") (pinfunction "2DIR_3") (pintype "bidirectional"))
      (node (ref "IC9") (pin "10") (pinfunction "OE_10") (pintype "input"))
      (node (ref "IC9") (pin "19") (pinfunction "VCCB_19") (pintype "power_in"))
      (node (ref "L1") (pin "1") (pinfunction "1_1") (pintype "passive"))
      (node (ref "L3") (pin "P$2") (pinfunction "2_P$2") (pintype "passive"))
      (node (ref "L4") (pin "P$2") (pinfunction "2_P$2") (pintype "passive"))
      (node (ref "LED2") (pin "2") (pinfunction "+_2") (pintype "passive"))
      (node (ref "R1") (pin "2") (pinfunction "2_2") (pintype "passive"))
      (node (ref "R13") (pin "1") (pinfunction "1_1") (pintype "passive"))
      (node (ref "R2") (pin "1") (pinfunction "1_1") (pintype "passive"))
      (node (ref "R42") (pin "1") (pinfunction "1_1") (pintype "passive"))
    )
    (net (code "3") (name "3V3_FEM") (class "Default")
      (node (ref "C16") (pin "1") (pinfunction "1_1") (pintype "passive"))
      (node (ref "C17") (pin "1") (pinfunction "1_1") (pintype "passive"))
      (node (ref "C4") (pin "2") (pinfunction "2_2") (pintype "passive"))
      (node (ref "C5") (pin "1") (pinfunction "1_1") (pintype "passive"))
      (node (ref "IC1") (pin "25") (pinfunction "VBAT_FEM_25") (pintype "bidirectional"))
      (node (ref "IC1") (pin "26") (pinfunction "VBAT_FEM_26") (pintype "bidirectional"))
      (node (ref "IC1") (pin "27") (pinfunction "VBAT_FEM_27") (pintype "bidirectional"))
      (node (ref "L1") (pin "2") (pinfunction "2_2") (pintype "passive"))
    )
    (net (code "4") (name "ADC0") (class "Default")
      (node (ref "IC1") (pin "59") (pinfunction "ADC0/GPIO1_59") (pintype "bidirectional"))
      (node (ref "R16") (pin "1") (pinfunction "1_1") (pintype "passive"))
    )
    (net (code "5") (name "ADC1") (class "Default")
      (node (ref "IC1") (pin "56") (pinfunction "ADC1/GPIO2_56") (pintype "bidirectional"))
      (node (ref "R17") (pin "1") (pinfunction "1_1") (pintype "passive"))
    )
    (net (code "6") (name "D+") (class "Default")
      (node (ref "CON1") (pin "3") (pinfunction "D+_3") (pintype "passive"))
      (node (ref "IC6") (pin "3") (pinfunction "I/O2_3") (pintype "bidirectional"))
      (node (ref "IC6") (pin "4") (pinfunction "I/O2_4") (pintype "bidirectional"))
      (node (ref "R10") (pin "1") (pinfunction "1_1") (pintype "passive"))
      (node (ref "TP7") (pin "P$1") (pinfunction "TP_P$1") (pintype "passive"))
    )
    (net (code "7") (name "D-") (class "Default")
      (node (ref "CON1") (pin "2") (pinfunction "D-_2") (pintype "passive"))
      (node (ref "IC6") (pin "1") (pinfunction "I/O1_1") (pintype "bidirectional"))
      (node (ref "IC6") (pin "6") (pinfunction "I/O1_6") (pintype "bidirectional"))
      (node (ref "R11") (pin "2") (pinfunction "2_2") (pintype "passive"))
      (node (ref "TP8") (pin "P$1") (pinfunction "TP_P$1") (pintype "passive"))
    )
    (net (code "8") (name "FTDI_1V8_VCORE") (class "Default")
      (node (ref "C13") (pin "1") (pinfunction "1_1") (pintype "passive"))
      (node (ref "C32") (pin "2") (pinfunction "2_2") (pintype "passive"))
      (node (ref "C33") (pin "2") (pinfunction "2_2") (pintype "passive"))
      (node (ref "C34") (pin "2") (pinfunction "2_2") (pintype "passive"))
      (node (ref "IC3") (pin "2") (pinfunction "VCORE_2") (pintype "power_in"))
      (node (ref "IC3") (pin "31") (pinfunction "VCORE_31") (pintype "power_in"))
      (node (ref "IC3") (pin "43") (pinfunction "VREGOUT_43") (pintype "power_in"))
    )
    (net (code "9") (name "GND") (class "Default")
      (node (ref "C0N2") (pin "2") (pinfunction "1_2") (pintype "passive"))
      (node (ref "C1") (pin "1") (pinfunction "1_1") (pintype "passive"))
      (node (ref "C10") (pin "1") (pinfunction "1_1") (pintype "passive"))
      (node (ref "C11") (pin "2") (pinfunction "2_2") (pintype "passive"))
      (node (ref "C12") (pin "2") (pinfunction "2_2") (pintype "passive"))
      (node (ref "C13") (pin "2") (pinfunction "2_2") (pintype "passive"))
      (node (ref "C14") (pin "1") (pinfunction "1_1") (pintype "passive"))
      (node (ref "C15") (pin "2") (pinfunction "2_2") (pintype "passive"))
      (node (ref "C16") (pin "2") (pinfunction "2_2") (pintype "passive"))
      (node (ref "C17") (pin "2") (pinfunction "2_2") (pintype "passive"))
      (node (ref "C18") (pin "2") (pinfunction "2_2") (pintype "passive"))
      (node (ref "C19") (pin "2") (pinfunction "2_2") (pintype "passive"))
      (node (ref "C2") (pin "2") (pinfunction "2_2") (pintype "passive"))
      (node (ref "C20") (pin "1") (pinfunction "1_1") (pintype "passive"))
      (node (ref "C21") (pin "2") (pinfunction "2_2") (pintype "passive"))
      (node (ref "C22") (pin "1") (pinfunction "1_1") (pintype "passive"))
      (node (ref "C23") (pin "2") (pinfunction "2_2") (pintype "passive"))
      (node (ref "C24") (pin "1") (pinfunction "1_1") (pintype "passive"))
      (node (ref "C25") (pin "1") (pinfunction "1_1") (pintype "passive"))
      (node (ref "C26") (pin "1") (pinfunction "1_1") (pintype "passive"))
      (node (ref "C27") (pin "1") (pinfunction "1_1") (pintype "passive"))
      (node (ref "C28") (pin "1") (pinfunction "1_1") (pintype "passive"))
      (node (ref "C29") (pin "1") (pinfunction "1_1") (pintype "passive"))
      (node (ref "C3") (pin "2") (pinfunction "2_2") (pintype "passive"))
      (node (ref "C30") (pin "1") (pinfunction "1_1") (pintype "passive"))
      (node (ref "C31") (pin "1") (pinfunction "1_1") (pintype "passive"))
      (node (ref "C32") (pin "1") (pinfunction "1_1") (pintype "passive"))
      (node (ref "C33") (pin "1") (pinfunction "1_1") (pintype "passive"))
      (node (ref "C34") (pin "1") (pinfunction "1_1") (pintype "passive"))
      (node (ref "C35") (pin "1") (pinfunction "1_1") (pintype "passive"))
      (node (ref "C36") (pin "1") (pinfunction "1_1") (pintype "passive"))
      (node (ref "C37") (pin "1") (pinfunction "1_1") (pintype "passive"))
      (node (ref "C38") (pin "1") (pinfunction "1_1") (pintype "passive"))
      (node (ref "C39") (pin "1") (pinfunction "1_1") (pintype "passive"))
      (node (ref "C4") (pin "1") (pinfunction "1_1") (pintype "passive"))
      (node (ref "C40") (pin "1") (pinfunction "1_1") (pintype "passive"))
      (node (ref "C41") (pin "P$2") (pinfunction "2_P$2") (pintype "passive"))
      (node (ref "C46") (pin "1") (pinfunction "1_1") (pintype "passive"))
      (node (ref "C47") (pin "1") (pinfunction "1_1") (pintype "passive"))
      (node (ref "C5") (pin "2") (pinfunction "2_2") (pintype "passive"))
      (node (ref "C50") (pin "1") (pinfunction "1_1") (pintype "passive"))
      (node (ref "C51") (pin "1") (pinfunction "1_1") (pintype "passive"))
      (node (ref "C55") (pin "1") (pinfunction "1_1") (pintype "passive"))
      (node (ref "C56") (pin "1") (pinfunction "1_1") (pintype "passive"))
      (node (ref "C6") (pin "1") (pinfunction "1_1") (pintype "passive"))
      (node (ref "C7") (pin "2") (pinfunction "2_2") (pintype "passive"))
      (node (ref "C8") (pin "1") (pinfunction "1_1") (pintype "passive"))
      (node (ref "C9") (pin "2") (pinfunction "2_2") (pintype "passive"))
      (node (ref "CON1") (pin "5") (pinfunction "GND_5") (pintype "passive"))
      (node (ref "CON1") (pin "SHELL") (pinfunction "SHIELD_SHELL") (pintype "passive"))
      (node (ref "CON1") (pin "SHELL1") (pinfunction "SHIELD_SHELL1") (pintype "passive"))
      (node (ref "CON1") (pin "SHELL2") (pinfunction "SHIELD_SHELL2") (pintype "passive"))
      (node (ref "CON1") (pin "SHELL3") (pinfunction "SHIELD_SHELL3") (pintype "passive"))
      (node (ref "CON3") (pin "C5") (pinfunction "GND_C5") (pintype "bidirectional"))
      (node (ref "CON3") (pin "S1") (pinfunction "SHIELD_S1") (pintype "bidirectional"))
      (node (ref "CON3") (pin "S2") (pinfunction "SHIELD_S2") (pintype "bidirectional"))
      (node (ref "CON3") (pin "S3") (pinfunction "SHIELD_S3") (pintype "bidirectional"))
      (node (ref "CON3") (pin "S4") (pinfunction "SHIELD_S4") (pintype "bidirectional"))
      (node (ref "CON3") (pin "S5") (pinfunction "SHIELD_S5") (pintype "bidirectional"))
      (node (ref "CON3") (pin "S6") (pinfunction "SHIELD_S6") (pintype "bidirectional"))
      (node (ref "CON4") (pin "2") (pinfunction "2_2") (pintype "passive"))
      (node (ref "CON4") (pin "3") (pinfunction "2_3") (pintype "passive"))
      (node (ref "CON5") (pin "2") (pinfunction "2_2") (pintype "passive"))
      (node (ref "CON5") (pin "3") (pinfunction "2_3") (pintype "passive"))
      (node (ref "D3") (pin "2") (pinfunction "2_2") (pintype "passive"))
      (node (ref "D4") (pin "2") (pinfunction "2_2") (pintype "passive"))
      (node (ref "IC1") (pin "1") (pinfunction "GND_1") (pintype "bidirectional"))
      (node (ref "IC1") (pin "100") (pinfunction "GND_100") (pintype "bidirectional"))
      (node (ref "IC1") (pin "101") (pinfunction "GND_101") (pintype "bidirectional"))
      (node (ref "IC1") (pin "102") (pinfunction "GND_102") (pintype "bidirectional"))
      (node (ref "IC1") (pin "103") (pinfunction "GND_103") (pintype "bidirectional"))
      (node (ref "IC1") (pin "104") (pinfunction "GND_104") (pintype "bidirectional"))
      (node (ref "IC1") (pin "2") (pinfunction "GND_2") (pintype "bidirectional"))
      (node (ref "IC1") (pin "28") (pinfunction "GND_28") (pintype "bidirectional"))
      (node (ref "IC1") (pin "29") (pinfunction "GND_29") (pintype "bidirectional"))
      (node (ref "IC1") (pin "30") (pinfunction "GND_30") (pintype "bidirectional"))
      (node (ref "IC1") (pin "31") (pinfunction "GND_31") (pintype "bidirectional"))
      (node (ref "IC1") (pin "32") (pinfunction "GND_32") (pintype "bidirectional"))
      (node (ref "IC1") (pin "33") (pinfunction "GND_33") (pintype "bidirectional"))
      (node (ref "IC1") (pin "34") (pinfunction "GND_34") (pintype "bidirectional"))
      (node (ref "IC1") (pin "35") (pinfunction "GND_35") (pintype "bidirectional"))
      (node (ref "IC1") (pin "36") (pinfunction "GND_36") (pintype "bidirectional"))
      (node (ref "IC1") (pin "37") (pinfunction "GND_37") (pintype "bidirectional"))
      (node (ref "IC1") (pin "38") (pinfunction "GND_38") (pintype "bidirectional"))
      (node (ref "IC1") (pin "40") (pinfunction "GND_40") (pintype "bidirectional"))
      (node (ref "IC1") (pin "41") (pinfunction "GND_41") (pintype "bidirectional"))
      (node (ref "IC1") (pin "42") (pinfunction "GND_42") (pintype "bidirectional"))
      (node (ref "IC1") (pin "45") (pinfunction "GND_45") (pintype "bidirectional"))
      (node (ref "IC1") (pin "46") (pinfunction "GND_46") (pintype "bidirectional"))
      (node (ref "IC1") (pin "51") (pinfunction "GND_51") (pintype "bidirectional"))
      (node (ref "IC1") (pin "52") (pinfunction "GND_52") (pintype "bidirectional"))
      (node (ref "IC1") (pin "57") (pinfunction "GND_57") (pintype "bidirectional"))
      (node (ref "IC1") (pin "86") (pinfunction "GND_86") (pintype "bidirectional"))
      (node (ref "IC1") (pin "88") (pinfunction "GND_88") (pintype "bidirectional"))
      (node (ref "IC1") (pin "90") (pinfunction "GND_90") (pintype "bidirectional"))
      (node (ref "IC1") (pin "92") (pinfunction "GND_92") (pintype "bidirectional"))
      (node (ref "IC1") (pin "93") (pinfunction "GND_93") (pintype "bidirectional"))
      (node (ref "IC1") (pin "94") (pinfunction "GND_94") (pintype "bidirectional"))
      (node (ref "IC1") (pin "95") (pinfunction "GND_95") (pintype "bidirectional"))
      (node (ref "IC1") (pin "96") (pinfunction "GND_96") (pintype "bidirectional"))
      (node (ref "IC1") (pin "97") (pinfunction "GND_97") (pintype "bidirectional"))
      (node (ref "IC1") (pin "98") (pinfunction "GND_98") (pintype "bidirectional"))
      (node (ref "IC1") (pin "99") (pinfunction "GND_99") (pintype "bidirectional"))
      (node (ref "IC2") (pin "1") (pinfunction "ADJ_1") (pintype "input"))
      (node (ref "IC3") (pin "10") (pinfunction "TEST_10") (pintype "input"))
      (node (ref "IC3") (pin "21") (pinfunction "GND_21") (pintype "power_in"))
      (node (ref "IC3") (pin "41") (pinfunction "GND_41") (pintype "power_in"))
      (node (ref "IC3") (pin "45") (pinfunction "GND_45") (pintype "power_in"))
      (node (ref "IC3") (pin "P$1") (pinfunction "GND_P$1") (pintype "power_in"))
      (node (ref "IC3") (pin "P$2") (pinfunction "GND_P$2") (pintype "power_in"))
      (node (ref "IC3") (pin "P$3") (pinfunction "GND_P$3") (pintype "power_in"))
      (node (ref "IC4") (pin "1") (pinfunction "ADJ_1") (pintype "input"))
      (node (ref "IC5") (pin "2") (pinfunction "1DIR_2") (pintype "bidirectional"))
      (node (ref "IC5") (pin "8") (pinfunction "GND_8") (pintype "bidirectional"))
      (node (ref "IC5") (pin "9") (pinfunction "GND_9") (pintype "bidirectional"))
      (node (ref "IC6") (pin "2") (pinfunction "GND_2") (pintype "power_in"))
      (node (ref "IC7") (pin "2") (pinfunction "VSS_2") (pintype "bidirectional"))
      (node (ref "IC8") (pin "2") (pinfunction "1DIR_2") (pintype "bidirectional"))
      (node (ref "IC8") (pin "8") (pinfunction "GND_8") (pintype "bidirectional"))
      (node (ref "IC8") (pin "9") (pinfunction "GND_9") (pintype "bidirectional"))
      (node (ref "IC9") (pin "11") (pinfunction "GND_11") (pintype "power_in"))
      (node (ref "LED1") (pin "1") (pinfunction "-_1") (pintype "passive"))
      (node (ref "MS1") (pin "4") (pinfunction "GND_4") (pintype "power_in"))
      (node (ref "Q1") (pin "2") (pinfunction "GND_2") (pintype "passive"))
      (node (ref "Q1") (pin "4") (pinfunction "GND_4") (pintype "passive"))
      (node (ref "R12") (pin "1") (pinfunction "1_1") (pintype "passive"))
      (node (ref "R20") (pin "2") (pinfunction "2_2") (pintype "passive"))
      (node (ref "R43") (pin "2") (pinfunction "2_2") (pintype "passive"))
      (node (ref "R6") (pin "1") (pinfunction "1_1") (pintype "passive"))
      (node (ref "R7") (pin "2") (pinfunction "2_2") (pintype "passive"))
      (node (ref "R8") (pin "2") (pinfunction "2_2") (pintype "passive"))
      (node (ref "S1") (pin "3") (pinfunction "3_3") (pintype "passive"))
      (node (ref "S1") (pin "4") (pinfunction "4_4") (pintype "passive"))
      (node (ref "S1") (pin "5") (pinfunction "3_5") (pintype "passive"))
      (node (ref "S1") (pin "6") (pinfunction "4_6") (pintype "passive"))
      (node (ref "T1") (pin "S") (pinfunction "S_S") (pintype "passive"))
      (node (ref "TP10") (pin "P$1") (pinfunction "TP_P$1") (pintype "passive"))
      (node (ref "TP11") (pin "P$1") (pinfunction "TP_P$1") (pintype "passive"))
      (node (ref "TP12") (pin "P$1") (pinfunction "TP_P$1") (pintype "passive"))
      (node (ref "TP6") (pin "P$1") (pinfunction "TP_P$1") (pintype "passive"))
    )
    (net (code "10") (name "GNSS_RX") (class "Default")
      (node (ref "C47") (pin "2") (pinfunction "2_2") (pintype "passive"))
      (node (ref "IC1") (pin "43") (pinfunction "RF_GNSS_ANT_43") (pintype "bidirectional"))
      (node (ref "R35") (pin "2") (pinfunction "2_2") (pintype "passive"))
    )
    (net (code "11") (name "GPIO_RX") (class "Default")
      (node (ref "IC5") (pin "4") (pinfunction "1A1_4") (pintype "bidirectional"))
      (node (ref "MS1") (pin "14") (pinfunction "GPIORX_14") (pintype "bidirectional"))
      (node (ref "R15") (pin "2") (pinfunction "2_2") (pintype "passive"))
    )
    (net (code "12") (name "GPIO_TX") (class "Default")
      (node (ref "IC5") (pin "6") (pinfunction "2A1_6") (pintype "bidirectional"))
      (node (ref "MS1") (pin "15") (pinfunction "GPIOTX_15") (pintype "bidirectional"))
      (node (ref "R14") (pin "2") (pinfunction "2_2") (pintype "passive"))
    )
    (net (code "13") (name "I2C_SCL") (class "Default")
      (node (ref "IC9") (pin "20") (pinfunction "B1_20") (pintype "bidirectional"))
      (node (ref "MS1") (pin "18") (pinfunction "GPIOSCL_18") (pintype "bidirectional"))
    )
    (net (code "14") (name "I2C_SDA") (class "Default")
      (node (ref "IC9") (pin "18") (pinfunction "B2_18") (pintype "bidirectional"))
      (node (ref "MS1") (pin "17") (pinfunction "GPIOSDA_17") (pintype "bidirectional"))
    )
    (net (code "15") (name "LTE_RXTX") (class "Default")
      (node (ref "C46") (pin "2") (pinfunction "2_2") (pintype "passive"))
      (node (ref "IC1") (pin "39") (pinfunction "RF_RXTX_39") (pintype "bidirectional"))
      (node (ref "R34") (pin "2") (pinfunction "2_2") (pintype "passive"))
    )
    (net (code "16") (name "M_I2C_SCL") (class "Default")
      (node (ref "IC1") (pin "15") (pinfunction "I2C0_SCL/GPIO43_15") (pintype "bidirectional"))
      (node (ref "IC9") (pin "1") (pinfunction "A1_1") (pintype "bidirectional"))
    )
    (net (code "17") (name "M_I2C_SDA") (class "Default")
      (node (ref "IC1") (pin "17") (pinfunction "I2C0_SDA/GPIO42_17") (pintype "bidirectional"))
      (node (ref "IC9") (pin "3") (pinfunction "A2_3") (pintype "bidirectional"))
    )
    (net (code "18") (name "M_SPI_CLK") (class "Default")
      (node (ref "IC1") (pin "76") (pinfunction "SPIM1_CLK/GPIO41_76") (pintype "bidirectional"))
      (node (ref "IC9") (pin "5") (pinfunction "A4_5") (pintype "bidirectional"))
    )
    (net (code "19") (name "M_SPI_CS") (class "Default")
      (node (ref "IC1") (pin "81") (pinfunction "SPIM1_EN/GPIO40_81") (pintype "bidirectional"))
      (node (ref "IC9") (pin "4") (pinfunction "A3_4") (pintype "bidirectional"))
    )
    (net (code "20") (name "M_SPI_MISO") (class "Default")
      (node (ref "IC1") (pin "74") (pinfunction "SPIM1_MISO/GPIO39_74") (pintype "bidirectional"))
      (node (ref "IC9") (pin "7") (pinfunction "A6_7") (pintype "bidirectional"))
    )
    (net (code "21") (name "M_SPI_MOSI") (class "Default")
      (node (ref "IC1") (pin "83") (pinfunction "SPIM1_MOSI/GPIO38_83") (pintype "bidirectional"))
      (node (ref "IC9") (pin "6") (pinfunction "A5_6") (pintype "bidirectional"))
    )
    (net (code "22") (name "M_WAKEUP") (class "Default")
      (node (ref "C55") (pin "2") (pinfunction "2_2") (pintype "passive"))
      (node (ref "IC1") (pin "7") (pinfunction "WAKEUP_7") (pintype "bidirectional"))
      (node (ref "IC9") (pin "8") (pinfunction "A7_8") (pintype "bidirectional"))
    )
    (net (code "23") (name "M_{slash}RESET") (class "Default")
      (node (ref "C56") (pin "2") (pinfunction "2_2") (pintype "passive"))
      (node (ref "IC1") (pin "9") (pinfunction "/RESET_9") (pintype "bidirectional"))
      (node (ref "IC9") (pin "9") (pinfunction "A8_9") (pintype "bidirectional"))
      (node (ref "S1") (pin "1") (pinfunction "1_1") (pintype "passive"))
      (node (ref "S1") (pin "2") (pinfunction "2_2") (pintype "passive"))
      (node (ref "TP5") (pin "P$1") (pinfunction "TP_P$1") (pintype "passive"))
    )
    (net (code "24") (name "Net-(C48-Pad1)") (class "Default")
      (node (ref "C48") (pin "1") (pinfunction "1_1") (pintype "passive"))
      (node (ref "CON4") (pin "1") (pinfunction "1_1") (pintype "passive"))
      (node (ref "D3") (pin "1") (pinfunction "1_1") (pintype "passive"))
    )
    (net (code "25") (name "Net-(C48-Pad2)") (class "Default")
      (node (ref "C48") (pin "2") (pinfunction "2_2") (pintype "passive"))
      (node (ref "C50") (pin "2") (pinfunction "2_2") (pintype "passive"))
      (node (ref "R34") (pin "1") (pinfunction "1_1") (pintype "passive"))
    )
    (net (code "26") (name "Net-(C49-Pad1)") (class "Default")
      (node (ref "C49") (pin "1") (pinfunction "1_1") (pintype "passive"))
      (node (ref "CON5") (pin "1") (pinfunction "1_1") (pintype "passive"))
      (node (ref "D4") (pin "1") (pinfunction "1_1") (pintype "passive"))
    )
    (net (code "27") (name "Net-(C49-Pad2)") (class "Default")
      (node (ref "C49") (pin "2") (pinfunction "2_2") (pintype "passive"))
      (node (ref "C51") (pin "2") (pinfunction "2_2") (pintype "passive"))
      (node (ref "R35") (pin "1") (pinfunction "1_1") (pintype "passive"))
    )
    (net (code "28") (name "Net-(CON1-VBUS)") (class "Default")
      (node (ref "CON1") (pin "1") (pinfunction "VBUS_1") (pintype "passive"))
      (node (ref "IC6") (pin "5") (pinfunction "VDD_5") (pintype "power_in"))
      (node (ref "L2") (pin "P$2") (pinfunction "2_P$2") (pintype "passive"))
      (node (ref "TP9") (pin "P$1") (pinfunction "TP_P$1") (pintype "passive"))
    )
    (net (code "29") (name "Net-(D2-C)") (class "Default")
      (node (ref "C20") (pin "2") (pinfunction "2_2") (pintype "passive"))
      (node (ref "D2") (pin "3") (pinfunction "C_3") (pintype "passive"))
      (node (ref "D7") (pin "K") (pinfunction "C_K") (pintype "passive"))
      (node (ref "D8") (pin "K") (pinfunction "C_K") (pintype "passive"))
      (node (ref "IC4") (pin "3") (pinfunction "IN_3") (pintype "input"))
    )
    (net (code "30") (name "Net-(D6-A)") (class "Default")
      (node (ref "D6") (pin "2") (pinfunction "A_2") (pintype "passive"))
      (node (ref "MS1") (pin "20") (pinfunction "GPIO6_20") (pintype "bidirectional"))
    )
    (net (code "31") (name "Net-(IC3-ADBUS0)") (class "Default")
      (node (ref "IC3") (pin "12") (pinfunction "ADBUS0_12") (pintype "bidirectional"))
      (node (ref "R14") (pin "1") (pinfunction "1_1") (pintype "passive"))
    )
    (net (code "32") (name "Net-(IC3-ADBUS1)") (class "Default")
      (node (ref "IC3") (pin "13") (pinfunction "ADBUS1_13") (pintype "bidirectional"))
      (node (ref "R15") (pin "1") (pinfunction "1_1") (pintype "passive"))
    )
    (net (code "33") (name "Net-(IC3-BDBUS0)") (class "Default")
      (node (ref "IC3") (pin "22") (pinfunction "BDBUS0_22") (pintype "bidirectional"))
      (node (ref "R18") (pin "1") (pinfunction "1_1") (pintype "passive"))
    )
    (net (code "34") (name "Net-(IC3-BDBUS1)") (class "Default")
      (node (ref "IC3") (pin "23") (pinfunction "BDBUS1_23") (pintype "bidirectional"))
      (node (ref "R19") (pin "1") (pinfunction "1_1") (pintype "passive"))
    )
    (net (code "35") (name "Net-(IC3-CDBUS0)") (class "Default")
      (node (ref "IC3") (pin "32") (pinfunction "CDBUS0_32") (pintype "bidirectional"))
      (node (ref "R22") (pin "1") (pinfunction "1_1") (pintype "passive"))
    )
    (net (code "36") (name "Net-(IC3-CDBUS1)") (class "Default")
      (node (ref "IC3") (pin "33") (pinfunction "CDBUS1_33") (pintype "bidirectional"))
      (node (ref "R23") (pin "1") (pinfunction "1_1") (pintype "passive"))
    )
    (net (code "37") (name "Net-(IC3-CDBUS2)") (class "Default")
      (node (ref "IC3") (pin "34") (pinfunction "CDBUS2_34") (pintype "bidirectional"))
      (node (ref "R24") (pin "1") (pinfunction "1_1") (pintype "passive"))
    )
    (net (code "38") (name "Net-(IC3-CDBUS3)") (class "Default")
      (node (ref "IC3") (pin "35") (pinfunction "CDBUS3_35") (pintype "bidirectional"))
      (node (ref "R25") (pin "1") (pinfunction "1_1") (pintype "passive"))
    )
    (net (code "39") (name "Net-(IC3-DM)") (class "Default")
      (node (ref "C8") (pin "2") (pinfunction "2_2") (pintype "passive"))
      (node (ref "IC3") (pin "7") (pinfunction "DM_7") (pintype "input"))
      (node (ref "R11") (pin "1") (pinfunction "1_1") (pintype "passive"))
    )
    (net (code "40") (name "Net-(IC3-DP)") (class "Default")
      (node (ref "C10") (pin "2") (pinfunction "2_2") (pintype "passive"))
      (node (ref "IC3") (pin "8") (pinfunction "DP_8") (pintype "input"))
      (node (ref "R10") (pin "2") (pinfunction "2_2") (pintype "passive"))
    )
    (net (code "41") (name "Net-(IC3-OSCI)") (class "Default")
      (node (ref "C24") (pin "2") (pinfunction "2_2") (pintype "passive"))
      (node (ref "IC3") (pin "3") (pinfunction "OSCI_3") (pintype "input"))
      (node (ref "Q1") (pin "1") (pinfunction "1_1") (pintype "passive"))
    )
    (net (code "42") (name "Net-(IC3-OSCO)") (class "Default")
      (node (ref "C26") (pin "2") (pinfunction "2_2") (pintype "passive"))
      (node (ref "IC3") (pin "4") (pinfunction "OSCO_4") (pintype "output"))
      (node (ref "Q1") (pin "3") (pinfunction "2_3") (pintype "passive"))
    )
    (net (code "43") (name "Net-(IC3-REF)") (class "Default")
      (node (ref "IC3") (pin "6") (pinfunction "REF_6") (pintype "input"))
      (node (ref "R12") (pin "2") (pinfunction "2_2") (pintype "passive"))
    )
    (net (code "44") (name "Net-(IC3-RESET#)") (class "Default")
      (node (ref "C28") (pin "2") (pinfunction "2_2") (pintype "passive"))
      (node (ref "IC3") (pin "11") (pinfunction "RESET#_11") (pintype "input"))
      (node (ref "R13") (pin "2") (pinfunction "2_2") (pintype "passive"))
    )
    (net (code "45") (name "Net-(IC3-VPHY)") (class "Default")
      (node (ref "C11") (pin "1") (pinfunction "1_1") (pintype "passive"))
      (node (ref "C27") (pin "2") (pinfunction "2_2") (pintype "passive"))
      (node (ref "IC3") (pin "5") (pinfunction "VPHY_5") (pintype "power_in"))
      (node (ref "L4") (pin "P$1") (pinfunction "1_P$1") (pintype "passive"))
    )
    (net (code "46") (name "Net-(IC3-VPLL)") (class "Default")
      (node (ref "C12") (pin "1") (pinfunction "1_1") (pintype "passive"))
      (node (ref "C31") (pin "2") (pinfunction "2_2") (pintype "passive"))
      (node (ref "IC3") (pin "9") (pinfunction "VPLL_9") (pintype "power_in"))
      (node (ref "L3") (pin "P$1") (pinfunction "1_P$1") (pintype "passive"))
    )
    (net (code "47") (name "Net-(IC5-1~{OE})") (class "Default")
      (node (ref "IC5") (pin "14") (pinfunction "2~{OE}_14") (pintype "bidirectional"))
      (node (ref "IC5") (pin "15") (pinfunction "1~{OE}_15") (pintype "bidirectional"))
      (node (ref "R7") (pin "1") (pinfunction "1_1") (pintype "passive"))
    )
    (net (code "48") (name "Net-(IC7-PROG)") (class "Default")
      (node (ref "IC7") (pin "5") (pinfunction "PROG_5") (pintype "bidirectional"))
      (node (ref "R6") (pin "2") (pinfunction "2_2") (pintype "passive"))
    )
    (net (code "49") (name "Net-(IC7-STAT)") (class "Default")
      (node (ref "IC7") (pin "1") (pinfunction "STAT_1") (pintype "bidirectional"))
      (node (ref "R5") (pin "2") (pinfunction "2_2") (pintype "passive"))
    )
    (net (code "50") (name "Net-(IC8-1~{OE})") (class "Default")
      (node (ref "IC8") (pin "14") (pinfunction "2~{OE}_14") (pintype "bidirectional"))
      (node (ref "IC8") (pin "15") (pinfunction "1~{OE}_15") (pintype "bidirectional"))
      (node (ref "R20") (pin "1") (pinfunction "1_1") (pintype "passive"))
    )
    (net (code "51") (name "Net-(L2-1)") (class "Default")
      (node (ref "D5") (pin "A") (pinfunction "A_A") (pintype "passive"))
      (node (ref "L2") (pin "P$1") (pinfunction "1_P$1") (pintype "passive"))
    )
    (net (code "52") (name "Net-(LED1-+)") (class "Default")
      (node (ref "LED1") (pin "2") (pinfunction "+_2") (pintype "passive"))
      (node (ref "R1") (pin "1") (pinfunction "1_1") (pintype "passive"))
    )
    (net (code "53") (name "Net-(LED2--)") (class "Default")
      (node (ref "LED2") (pin "1") (pinfunction "-_1") (pintype "passive"))
      (node (ref "R3") (pin "1") (pinfunction "1_1") (pintype "passive"))
    )
    (net (code "54") (name "Net-(LED3--)") (class "Default")
      (node (ref "LED3") (pin "1") (pinfunction "-_1") (pintype "passive"))
      (node (ref "R5") (pin "1") (pinfunction "1_1") (pintype "passive"))
    )
    (net (code "55") (name "Net-(MS1-3V)") (class "Default")
      (node (ref "MS1") (pin "2") (pinfunction "3V_2") (pintype "power_in"))
      (node (ref "R2") (pin "2") (pinfunction "2_2") (pintype "passive"))
    )
    (net (code "56") (name "Net-(MS1-GPIOA0)") (class "Default")
      (node (ref "MS1") (pin "5") (pinfunction "GPIOA0_5") (pintype "bidirectional"))
      (node (ref "R16") (pin "2") (pinfunction "2_2") (pintype "passive"))
    )
    (net (code "57") (name "Net-(MS1-GPIOA1)") (class "Default")
      (node (ref "MS1") (pin "6") (pinfunction "GPIOA1_6") (pintype "bidirectional"))
      (node (ref "R17") (pin "2") (pinfunction "2_2") (pintype "passive"))
    )
    (net (code "58") (name "Net-(MS1-USB)") (class "Default")
      (node (ref "MS1") (pin "26") (pinfunction "USB_26") (pintype "power_in"))
      (node (ref "R4") (pin "1") (pinfunction "1_1") (pintype "passive"))
    )
    (net (code "59") (name "Net-(R3-Pad2)") (class "Default")
      (node (ref "R3") (pin "2") (pinfunction "2_2") (pintype "passive"))
      (node (ref "T1") (pin "D") (pinfunction "D_D") (pintype "passive"))
    )
    (net (code "60") (name "Net-(R8-Pad1)") (class "Default")
      (node (ref "R8") (pin "1") (pinfunction "1_1") (pintype "passive"))
      (node (ref "R9") (pin "2") (pinfunction "2_2") (pintype "passive"))
      (node (ref "T1") (pin "G") (pinfunction "G_G") (pintype "passive"))
    )
    (net (code "61") (name "Net-(R42-Pad2)") (class "Default")
      (node (ref "R42") (pin "2") (pinfunction "2_2") (pintype "passive"))
      (node (ref "S2") (pin "1") (pinfunction "1_1") (pintype "passive"))
      (node (ref "S2") (pin "2") (pinfunction "2_2") (pintype "passive"))
    )
    (net (code "62") (name "SIM_CLK") (class "Default")
      (node (ref "CON3") (pin "C3") (pinfunction "CLK_C3") (pintype "bidirectional"))
      (node (ref "IC1") (pin "75") (pinfunction "SIMCLK_75") (pintype "bidirectional"))
    )
    (net (code "63") (name "SIM_IO") (class "Default")
      (node (ref "CON3") (pin "C7") (pinfunction "I/O_C7") (pintype "bidirectional"))
      (node (ref "IC1") (pin "79") (pinfunction "SIMIO_79") (pintype "bidirectional"))
    )
    (net (code "64") (name "SIM_RST") (class "Default")
      (node (ref "CON3") (pin "C2") (pinfunction "RST_C2") (pintype "bidirectional"))
      (node (ref "IC1") (pin "77") (pinfunction "SIMRST_77") (pintype "bidirectional"))
    )
    (net (code "65") (name "SPI_CLK") (class "Default")
      (node (ref "IC9") (pin "16") (pinfunction "B4_16") (pintype "bidirectional"))
      (node (ref "MS1") (pin "11") (pinfunction "GPIOSCK_11") (pintype "bidirectional"))
    )
    (net (code "66") (name "SPI_CS") (class "Default")
      (node (ref "IC9") (pin "17") (pinfunction "B3_17") (pintype "bidirectional"))
      (node (ref "MS1") (pin "10") (pinfunction "GPIOA5_10") (pintype "bidirectional"))
    )
    (net (code "67") (name "SPI_MISO") (class "Default")
      (node (ref "IC9") (pin "14") (pinfunction "B6_14") (pintype "bidirectional"))
      (node (ref "MS1") (pin "13") (pinfunction "GPIOMISO_13") (pintype "bidirectional"))
    )
    (net (code "68") (name "SPI_MOSI") (class "Default")
      (node (ref "IC9") (pin "15") (pinfunction "B5_15") (pintype "bidirectional"))
      (node (ref "MS1") (pin "12") (pinfunction "GPIOMOSI_12") (pintype "bidirectional"))
    )
    (net (code "69") (name "STATUS") (class "Default")
      (node (ref "IC1") (pin "58") (pinfunction "STATUS_58") (pintype "bidirectional"))
      (node (ref "R9") (pin "1") (pinfunction "1_1") (pintype "passive"))
    )
    (net (code "70") (name "U1_3V3_RX") (class "Default")
      (node (ref "IC5") (pin "5") (pinfunction "1A2_5") (pintype "bidirectional"))
      (node (ref "R19") (pin "2") (pinfunction "2_2") (pintype "passive"))
    )
    (net (code "71") (name "U1_3V3_TX") (class "Default")
      (node (ref "IC5") (pin "7") (pinfunction "2A2_7") (pintype "bidirectional"))
      (node (ref "R18") (pin "2") (pinfunction "2_2") (pintype "passive"))
    )
    (net (code "72") (name "U2_3V3_CTS") (class "Default")
      (node (ref "IC8") (pin "4") (pinfunction "1A1_4") (pintype "bidirectional"))
      (node (ref "R25") (pin "2") (pinfunction "2_2") (pintype "passive"))
    )
    (net (code "73") (name "U2_3V3_RTS") (class "Default")
      (node (ref "IC8") (pin "6") (pinfunction "2A1_6") (pintype "bidirectional"))
      (node (ref "R24") (pin "2") (pinfunction "2_2") (pintype "passive"))
    )
    (net (code "74") (name "U2_3V3_RX") (class "Default")
      (node (ref "IC8") (pin "5") (pinfunction "1A2_5") (pintype "bidirectional"))
      (node (ref "R23") (pin "2") (pinfunction "2_2") (pintype "passive"))
    )
    (net (code "75") (name "U2_3V3_TX") (class "Default")
      (node (ref "IC8") (pin "7") (pinfunction "2A2_7") (pintype "bidirectional"))
      (node (ref "R22") (pin "2") (pinfunction "2_2") (pintype "passive"))
    )
    (net (code "76") (name "UART0_RX") (class "Default")
      (node (ref "IC1") (pin "22") (pinfunction "UART0_RX/GPIO23_22") (pintype "bidirectional"))
      (node (ref "IC5") (pin "11") (pinfunction "2B1_11") (pintype "bidirectional"))
    )
    (net (code "77") (name "UART0_TX") (class "Default")
      (node (ref "IC1") (pin "21") (pinfunction "UART0_TX/GPIO24_21") (pintype "bidirectional"))
      (node (ref "IC5") (pin "13") (pinfunction "1B1_13") (pintype "bidirectional"))
    )
    (net (code "78") (name "UART1_CTS") (class "Default")
      (node (ref "IC1") (pin "65") (pinfunction "UART1_CTS_65") (pintype "bidirectional"))
      (node (ref "TP2") (pin "P$1") (pinfunction "TP_P$1") (pintype "passive"))
    )
    (net (code "79") (name "UART1_RTS") (class "Default")
      (node (ref "IC1") (pin "61") (pinfunction "UART1_RTS_61") (pintype "bidirectional"))
      (node (ref "TP4") (pin "P$1") (pinfunction "TP_P$1") (pintype "passive"))
    )
    (net (code "80") (name "UART1_RX") (class "Default")
      (node (ref "IC1") (pin "63") (pinfunction "UART1_RX_63") (pintype "bidirectional"))
      (node (ref "IC5") (pin "10") (pinfunction "2B2_10") (pintype "bidirectional"))
      (node (ref "TP1") (pin "P$1") (pinfunction "TP_P$1") (pintype "passive"))
    )
    (net (code "81") (name "UART1_TX") (class "Default")
      (node (ref "IC1") (pin "60") (pinfunction "UART1_TX_60") (pintype "bidirectional"))
      (node (ref "IC5") (pin "12") (pinfunction "1B2_12") (pintype "bidirectional"))
      (node (ref "TP3") (pin "P$1") (pinfunction "TP_P$1") (pintype "passive"))
    )
    (net (code "82") (name "UART2_CTS") (class "Default")
      (node (ref "IC1") (pin "53") (pinfunction "UART2_CTS_53") (pintype "bidirectional"))
      (node (ref "IC8") (pin "11") (pinfunction "2B1_11") (pintype "bidirectional"))
    )
    (net (code "83") (name "UART2_RTS") (class "Default")
      (node (ref "IC1") (pin "55") (pinfunction "UART2_RTS_55") (pintype "bidirectional"))
      (node (ref "IC8") (pin "13") (pinfunction "1B1_13") (pintype "bidirectional"))
    )
    (net (code "84") (name "UART2_RX") (class "Default")
      (node (ref "IC1") (pin "50") (pinfunction "UART2_RX_50") (pintype "bidirectional"))
      (node (ref "IC8") (pin "10") (pinfunction "2B2_10") (pintype "bidirectional"))
    )
    (net (code "85") (name "UART2_TX") (class "Default")
      (node (ref "IC1") (pin "48") (pinfunction "UART2_TX_48") (pintype "bidirectional"))
      (node (ref "IC8") (pin "12") (pinfunction "1B2_12") (pintype "bidirectional"))
    )
    (net (code "86") (name "USB_5V") (class "Default")
      (node (ref "C39") (pin "2") (pinfunction "2_2") (pintype "passive"))
      (node (ref "D5") (pin "K") (pinfunction "C_K") (pintype "passive"))
      (node (ref "D7") (pin "A") (pinfunction "A_A") (pintype "passive"))
      (node (ref "IC7") (pin "4") (pinfunction "VDD_4") (pintype "bidirectional"))
      (node (ref "LED3") (pin "2") (pinfunction "+_2") (pintype "passive"))
      (node (ref "R4") (pin "2") (pinfunction "2_2") (pintype "passive"))
    )
    (net (code "87") (name "VBAT") (class "Default")
      (node (ref "C0N2") (pin "1") (pinfunction "2_1") (pintype "passive"))
      (node (ref "C15") (pin "1") (pinfunction "1_1") (pintype "passive"))
      (node (ref "D8") (pin "A") (pinfunction "A_A") (pintype "passive"))
      (node (ref "IC7") (pin "3") (pinfunction "VBAT_3") (pintype "bidirectional"))
      (node (ref "MS1") (pin "28") (pinfunction "VBAT_28") (pintype "power_in"))
    )
    (net (code "88") (name "VCC_SIM") (class "Default")
      (node (ref "C3") (pin "1") (pinfunction "1_1") (pintype "passive"))
      (node (ref "CON3") (pin "C1") (pinfunction "VCC_C1") (pintype "bidirectional"))
      (node (ref "IC1") (pin "72") (pinfunction "VSIM_72") (pintype "bidirectional"))
    )
    (net (code "89") (name "WAKEUP_3V3") (class "Default")
      (node (ref "D6") (pin "1") (pinfunction "C_1") (pintype "passive"))
      (node (ref "IC9") (pin "13") (pinfunction "B7_13") (pintype "bidirectional"))
      (node (ref "R43") (pin "1") (pinfunction "1_1") (pintype "passive"))
      (node (ref "S2") (pin "3") (pinfunction "3_3") (pintype "passive"))
      (node (ref "S2") (pin "4") (pinfunction "4_4") (pintype "passive"))
      (node (ref "S2") (pin "5") (pinfunction "3_5") (pintype "passive"))
      (node (ref "S2") (pin "6") (pinfunction "4_6") (pintype "passive"))
    )
    (net (code "90") (name "unconnected-(CON1-ID-Pad4)") (class "Default")
      (node (ref "CON1") (pin "4") (pinfunction "ID_4") (pintype "passive"))
    )
    (net (code "91") (name "unconnected-(CON3-VPP-PadC6)") (class "Default")
      (node (ref "CON3") (pin "C6") (pinfunction "VPP_C6") (pintype "bidirectional"))
    )
    (net (code "92") (name "unconnected-(IC1-AT_IN-Pad6)") (class "Default")
      (node (ref "IC1") (pin "6") (pinfunction "AT_IN_6") (pintype "bidirectional"))
    )
    (net (code "93") (name "unconnected-(IC1-DEBUG_SEL-Pad84)") (class "Default")
      (node (ref "IC1") (pin "84") (pinfunction "DEBUG_SEL_84") (pintype "bidirectional"))
    )
    (net (code "94") (name "unconnected-(IC1-DEBUG_{slash}RST-Pad82)") (class "Default")
      (node (ref "IC1") (pin "82") (pinfunction "DEBUG_/RST_82") (pintype "bidirectional"))
    )
    (net (code "95") (name "unconnected-(IC1-EJ_TCK-Pad10)") (class "Default")
      (node (ref "IC1") (pin "10") (pinfunction "EJ_TCK_10") (pintype "bidirectional"))
    )
    (net (code "96") (name "unconnected-(IC1-EJ_TDI-Pad14)") (class "Default")
      (node (ref "IC1") (pin "14") (pinfunction "EJ_TDI_14") (pintype "bidirectional"))
    )
    (net (code "97") (name "unconnected-(IC1-EJ_TDO-Pad12)") (class "Default")
      (node (ref "IC1") (pin "12") (pinfunction "EJ_TDO_12") (pintype "bidirectional"))
    )
    (net (code "98") (name "unconnected-(IC1-EJ_TMS-Pad16)") (class "Default")
      (node (ref "IC1") (pin "16") (pinfunction "EJ_TMS_16") (pintype "bidirectional"))
    )
    (net (code "99") (name "unconnected-(IC1-EJ_TRST-Pad18)") (class "Default")
      (node (ref "IC1") (pin "18") (pinfunction "EJ_TRST_18") (pintype "bidirectional"))
    )
    (net (code "100") (name "unconnected-(IC1-EXT_ALARM-Pad13)") (class "Default")
      (node (ref "IC1") (pin "13") (pinfunction "EXT_ALARM_13") (pintype "bidirectional"))
    )
    (net (code "101") (name "unconnected-(IC1-PMU_AT_OUT-Pad8)") (class "Default")
      (node (ref "IC1") (pin "8") (pinfunction "PMU_AT_OUT_8") (pintype "bidirectional"))
    )
    (net (code "102") (name "unconnected-(IC1-RESERVED1-Pad62)") (class "Default")
      (node (ref "IC1") (pin "62") (pinfunction "RESERVED1_62") (pintype "bidirectional"))
    )
    (net (code "103") (name "unconnected-(IC1-RESERVED2-Pad64)") (class "Default")
      (node (ref "IC1") (pin "64") (pinfunction "RESERVED2_64") (pintype "bidirectional"))
    )
    (net (code "104") (name "unconnected-(IC1-RESERVED3-Pad67)") (class "Default")
      (node (ref "IC1") (pin "67") (pinfunction "RESERVED3_67") (pintype "bidirectional"))
    )
    (net (code "105") (name "unconnected-(IC1-RESERVED4-Pad69)") (class "Default")
      (node (ref "IC1") (pin "69") (pinfunction "RESERVED4_69") (pintype "bidirectional"))
    )
    (net (code "106") (name "unconnected-(IC1-RESERVED5-Pad44)") (class "Default")
      (node (ref "IC1") (pin "44") (pinfunction "RESERVED5_44") (pintype "bidirectional"))
    )
    (net (code "107") (name "unconnected-(IC1-RESERVED6-Pad47)") (class "Default")
      (node (ref "IC1") (pin "47") (pinfunction "RESERVED6_47") (pintype "bidirectional"))
    )
    (net (code "108") (name "unconnected-(IC1-RESERVED7-Pad49)") (class "Default")
      (node (ref "IC1") (pin "49") (pinfunction "RESERVED7_49") (pintype "bidirectional"))
    )
    (net (code "109") (name "unconnected-(IC1-RESERVED8-Pad66)") (class "Default")
      (node (ref "IC1") (pin "66") (pinfunction "RESERVED8_66") (pintype "bidirectional"))
    )
    (net (code "110") (name "unconnected-(IC1-RESERVED9-Pad68)") (class "Default")
      (node (ref "IC1") (pin "68") (pinfunction "RESERVED9_68") (pintype "bidirectional"))
    )
    (net (code "111") (name "unconnected-(IC1-RESERVED10-Pad71)") (class "Default")
      (node (ref "IC1") (pin "71") (pinfunction "RESERVED10_71") (pintype "bidirectional"))
    )
    (net (code "112") (name "unconnected-(IC1-RESERVED11-Pad73)") (class "Default")
      (node (ref "IC1") (pin "73") (pinfunction "RESERVED11_73") (pintype "bidirectional"))
    )
    (net (code "113") (name "unconnected-(IC1-RESERVED12-Pad89)") (class "Default")
      (node (ref "IC1") (pin "89") (pinfunction "RESERVED12_89") (pintype "bidirectional"))
    )
    (net (code "114") (name "unconnected-(IC1-RESERVED13-Pad78)") (class "Default")
      (node (ref "IC1") (pin "78") (pinfunction "RESERVED13_78") (pintype "bidirectional"))
    )
    (net (code "115") (name "unconnected-(IC1-RESERVED14-Pad11)") (class "Default")
      (node (ref "IC1") (pin "11") (pinfunction "RESERVED14_11") (pintype "bidirectional"))
    )
    (net (code "116") (name "unconnected-(IC1-RESERVED15-Pad54)") (class "Default")
      (node (ref "IC1") (pin "54") (pinfunction "RESERVED15_54") (pintype "bidirectional"))
    )
    (net (code "117") (name "unconnected-(IC1-RESERVED16-Pad70)") (class "Default")
      (node (ref "IC1") (pin "70") (pinfunction "RESERVED16_70") (pintype "bidirectional"))
    )
    (net (code "118") (name "unconnected-(IC1-RFFE_SCLK-Pad23)") (class "Default")
      (node (ref "IC1") (pin "23") (pinfunction "RFFE_SCLK_23") (pintype "bidirectional"))
    )
    (net (code "119") (name "unconnected-(IC1-RFFE_SDATA-Pad24)") (class "Default")
      (node (ref "IC1") (pin "24") (pinfunction "RFFE_SDATA_24") (pintype "bidirectional"))
    )
    (net (code "120") (name "unconnected-(IC1-UART0_CTS{slash}GPIO25-Pad20)") (class "Default")
      (node (ref "IC1") (pin "20") (pinfunction "UART0_CTS/GPIO25_20") (pintype "bidirectional"))
    )
    (net (code "121") (name "unconnected-(IC1-UART0_RTS{slash}GPIO26-Pad19)") (class "Default")
      (node (ref "IC1") (pin "19") (pinfunction "UART0_RTS/GPIO26_19") (pintype "bidirectional"))
    )
    (net (code "122") (name "unconnected-(IC1-VBACKUP-Pad85)") (class "Default")
      (node (ref "IC1") (pin "85") (pinfunction "VBACKUP_85") (pintype "bidirectional"))
    )
    (net (code "123") (name "unconnected-(IC1-VCAP-Pad80)") (class "Default")
      (node (ref "IC1") (pin "80") (pinfunction "VCAP_80") (pintype "bidirectional"))
    )
    (net (code "124") (name "unconnected-(IC1-VDDIO-Pad87)") (class "Default")
      (node (ref "IC1") (pin "87") (pinfunction "VDDIO_87") (pintype "bidirectional"))
    )
    (net (code "125") (name "unconnected-(IC1-VDD_AUX-Pad91)") (class "Default")
      (node (ref "IC1") (pin "91") (pinfunction "VDD_AUX_91") (pintype "bidirectional"))
    )
    (net (code "126") (name "unconnected-(IC3-ADBUS2-Pad14)") (class "Default")
      (node (ref "IC3") (pin "14") (pinfunction "ADBUS2_14") (pintype "bidirectional"))
    )
    (net (code "127") (name "unconnected-(IC3-ADBUS3-Pad15)") (class "Default")
      (node (ref "IC3") (pin "15") (pinfunction "ADBUS3_15") (pintype "bidirectional"))
    )
    (net (code "128") (name "unconnected-(IC3-ADBUS4-Pad17)") (class "Default")
      (node (ref "IC3") (pin "17") (pinfunction "ADBUS4_17") (pintype "bidirectional"))
    )
    (net (code "129") (name "unconnected-(IC3-ADBUS5-Pad18)") (class "Default")
      (node (ref "IC3") (pin "18") (pinfunction "ADBUS5_18") (pintype "bidirectional"))
    )
    (net (code "130") (name "unconnected-(IC3-ADBUS6-Pad19)") (class "Default")
      (node (ref "IC3") (pin "19") (pinfunction "ADBUS6_19") (pintype "bidirectional"))
    )
    (net (code "131") (name "unconnected-(IC3-ADBUS7-Pad20)") (class "Default")
      (node (ref "IC3") (pin "20") (pinfunction "ADBUS7_20") (pintype "bidirectional"))
    )
    (net (code "132") (name "unconnected-(IC3-BDBUS2-Pad24)") (class "Default")
      (node (ref "IC3") (pin "24") (pinfunction "BDBUS2_24") (pintype "bidirectional"))
    )
    (net (code "133") (name "unconnected-(IC3-BDBUS3-Pad25)") (class "Default")
      (node (ref "IC3") (pin "25") (pinfunction "BDBUS3_25") (pintype "bidirectional"))
    )
    (net (code "134") (name "unconnected-(IC3-BDBUS4-Pad26)") (class "Default")
      (node (ref "IC3") (pin "26") (pinfunction "BDBUS4_26") (pintype "bidirectional"))
    )
    (net (code "135") (name "unconnected-(IC3-BDBUS5-Pad27)") (class "Default")
      (node (ref "IC3") (pin "27") (pinfunction "BDBUS5_27") (pintype "bidirectional"))
    )
    (net (code "136") (name "unconnected-(IC3-BDBUS6-Pad28)") (class "Default")
      (node (ref "IC3") (pin "28") (pinfunction "BDBUS6_28") (pintype "bidirectional"))
    )
    (net (code "137") (name "unconnected-(IC3-BDBUS7-Pad29)") (class "Default")
      (node (ref "IC3") (pin "29") (pinfunction "BDBUS7_29") (pintype "bidirectional"))
    )
    (net (code "138") (name "unconnected-(IC3-CDBUS4-Pad37)") (class "Default")
      (node (ref "IC3") (pin "37") (pinfunction "CDBUS4_37") (pintype "bidirectional"))
    )
    (net (code "139") (name "unconnected-(IC3-CDBUS5-Pad38)") (class "Default")
      (node (ref "IC3") (pin "38") (pinfunction "CDBUS5_38") (pintype "bidirectional"))
    )
    (net (code "140") (name "unconnected-(IC3-CDBUS6-Pad39)") (class "Default")
      (node (ref "IC3") (pin "39") (pinfunction "CDBUS6_39") (pintype "bidirectional"))
    )
    (net (code "141") (name "unconnected-(IC3-CDBUS7-Pad40)") (class "Default")
      (node (ref "IC3") (pin "40") (pinfunction "CDBUS7_40") (pintype "bidirectional"))
    )
    (net (code "142") (name "unconnected-(IC3-DDBUS0-Pad42)") (class "Default")
      (node (ref "IC3") (pin "42") (pinfunction "DDBUS0_42") (pintype "bidirectional"))
    )
    (net (code "143") (name "unconnected-(IC3-DDBUS1-Pad46)") (class "Default")
      (node (ref "IC3") (pin "46") (pinfunction "DDBUS1_46") (pintype "bidirectional"))
    )
    (net (code "144") (name "unconnected-(IC3-DDBUS2-Pad47)") (class "Default")
      (node (ref "IC3") (pin "47") (pinfunction "DDBUS2_47") (pintype "bidirectional"))
    )
    (net (code "145") (name "unconnected-(IC3-DDBUS3-Pad48)") (class "Default")
      (node (ref "IC3") (pin "48") (pinfunction "DDBUS3_48") (pintype "bidirectional"))
    )
    (net (code "146") (name "unconnected-(IC3-DDBUS4-Pad49)") (class "Default")
      (node (ref "IC3") (pin "49") (pinfunction "DDBUS4_49") (pintype "bidirectional"))
    )
    (net (code "147") (name "unconnected-(IC3-DDBUS5-Pad51)") (class "Default")
      (node (ref "IC3") (pin "51") (pinfunction "DDBUS5_51") (pintype "bidirectional"))
    )
    (net (code "148") (name "unconnected-(IC3-DDBUS6-Pad52)") (class "Default")
      (node (ref "IC3") (pin "52") (pinfunction "DDBUS6_52") (pintype "bidirectional"))
    )
    (net (code "149") (name "unconnected-(IC3-DDBUS7-Pad53)") (class "Default")
      (node (ref "IC3") (pin "53") (pinfunction "DDBUS7_53") (pintype "bidirectional"))
    )
    (net (code "150") (name "unconnected-(IC3-EECLK-Pad56)") (class "Default")
      (node (ref "IC3") (pin "56") (pinfunction "EECLK_56") (pintype "bidirectional"))
    )
    (net (code "151") (name "unconnected-(IC3-EECS-Pad1)") (class "Default")
      (node (ref "IC3") (pin "1") (pinfunction "EECS_1") (pintype "bidirectional"))
    )
    (net (code "152") (name "unconnected-(IC3-EEDATA-Pad55)") (class "Default")
      (node (ref "IC3") (pin "55") (pinfunction "EEDATA_55") (pintype "output"))
    )
    (net (code "153") (name "unconnected-(IC3-PWREN#-Pad54)") (class "Default")
      (node (ref "IC3") (pin "54") (pinfunction "PWREN#_54") (pintype "output"))
    )
    (net (code "154") (name "unconnected-(IC3-SUSPEND#-Pad30)") (class "Default")
      (node (ref "IC3") (pin "30") (pinfunction "SUSPEND#_30") (pintype "output"))
    )
    (net (code "155") (name "unconnected-(MS1-AREF-Pad3)") (class "Default")
      (node (ref "MS1") (pin "3") (pinfunction "AREF_3") (pintype "passive"))
    )
    (net (code "156") (name "unconnected-(MS1-EN-Pad27)") (class "Default")
      (node (ref "MS1") (pin "27") (pinfunction "EN_27") (pintype "passive"))
    )
    (net (code "157") (name "unconnected-(MS1-GPIO5-Pad19)") (class "Default")
      (node (ref "MS1") (pin "19") (pinfunction "GPIO5_19") (pintype "bidirectional"))
    )
    (net (code "158") (name "unconnected-(MS1-GPIO9-Pad21)") (class "Default")
      (node (ref "MS1") (pin "21") (pinfunction "GPIO9_21") (pintype "bidirectional"))
    )
    (net (code "159") (name "unconnected-(MS1-GPIO10-Pad22)") (class "Default")
      (node (ref "MS1") (pin "22") (pinfunction "GPIO10_22") (pintype "bidirectional"))
    )
    (net (code "160") (name "unconnected-(MS1-GPIO11-Pad23)") (class "Default")
      (node (ref "MS1") (pin "23") (pinfunction "GPIO11_23") (pintype "bidirectional"))
    )
    (net (code "161") (name "unconnected-(MS1-GPIO12-Pad24)") (class "Default")
      (node (ref "MS1") (pin "24") (pinfunction "GPIO12_24") (pintype "bidirectional"))
    )
    (net (code "162") (name "unconnected-(MS1-GPIO13-Pad25)") (class "Default")
      (node (ref "MS1") (pin "25") (pinfunction "GPIO13_25") (pintype "bidirectional"))
    )
    (net (code "163") (name "unconnected-(MS1-GPIOA2-Pad7)") (class "Default")
      (node (ref "MS1") (pin "7") (pinfunction "GPIOA2_7") (pintype "bidirectional"))
    )
    (net (code "164") (name "unconnected-(MS1-GPIOA3-Pad8)") (class "Default")
      (node (ref "MS1") (pin "8") (pinfunction "GPIOA3_8") (pintype "bidirectional"))
    )
    (net (code "165") (name "unconnected-(MS1-GPIOA4-Pad9)") (class "Default")
      (node (ref "MS1") (pin "9") (pinfunction "GPIOA4_9") (pintype "bidirectional"))
    )
    (net (code "166") (name "unconnected-(MS1-NC-Pad16)") (class "Default")
      (node (ref "MS1") (pin "16") (pinfunction "NC_16") (pintype "passive"))
    )
    (net (code "167") (name "{slash}RESET_3V3") (class "Default")
      (node (ref "IC9") (pin "12") (pinfunction "B8_12") (pintype "bidirectional"))
      (node (ref "MS1") (pin "1") (pinfunction "~{RESET}_1") (pintype "input"))
    )
  )
)
